# 21_Power-PMIC_RK806-1.net
KiCad netlist of a schematic drawn in Altium Designer
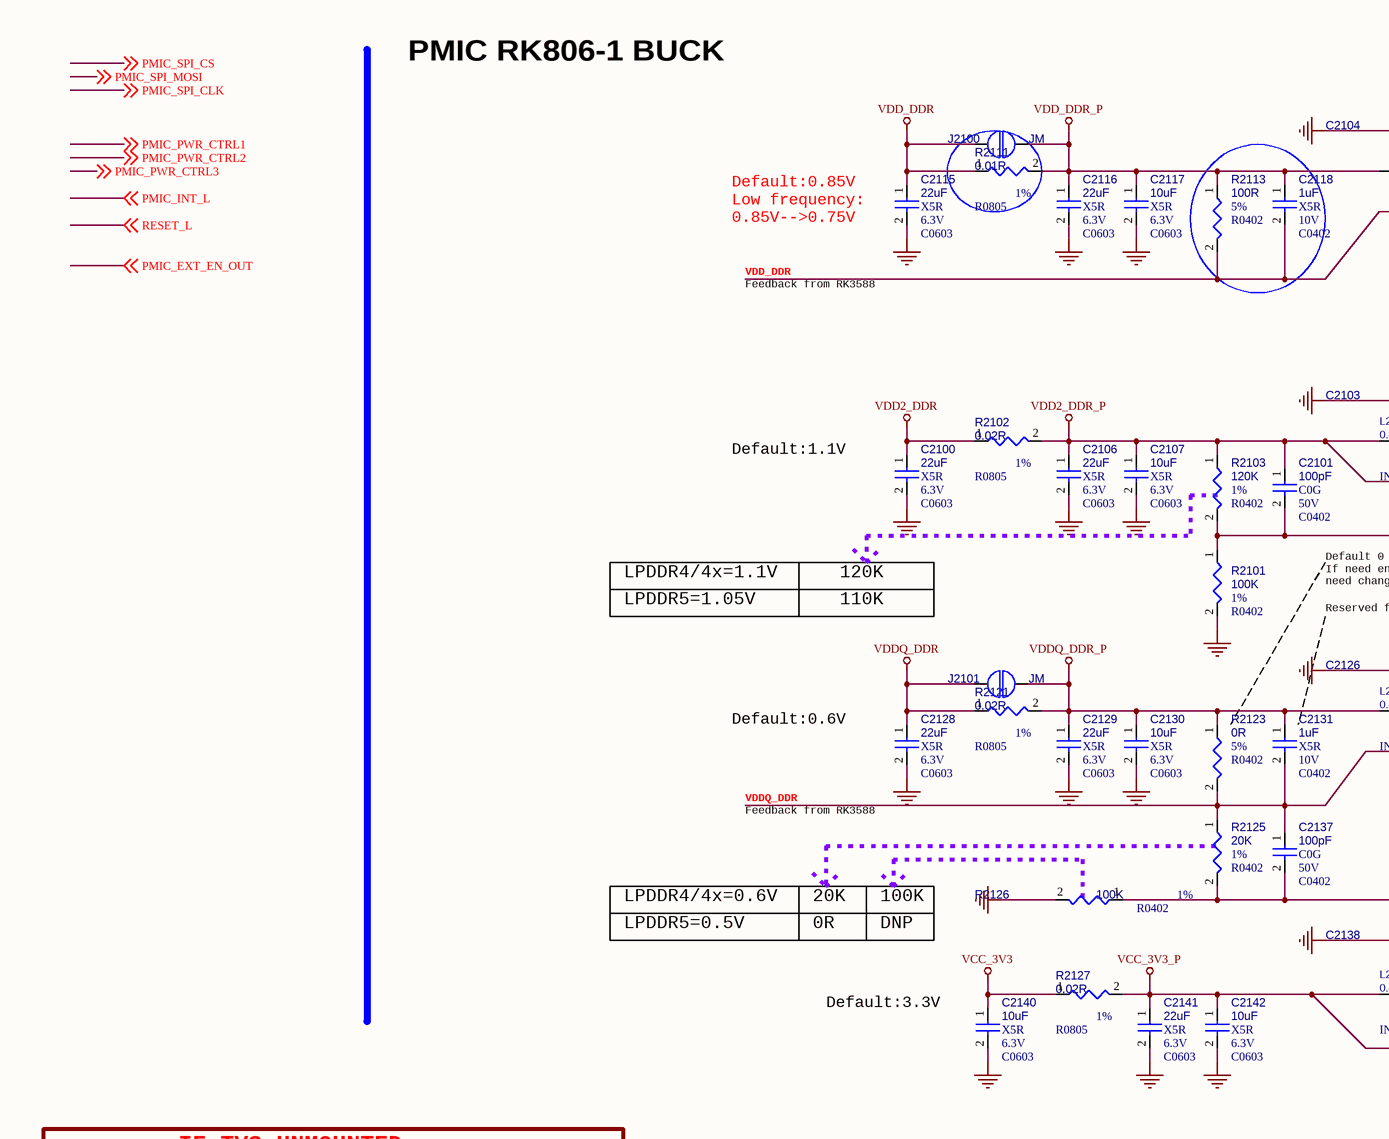
[diagram p0: 21.Power-PMIC_RK806-1.SchDoc, top left]
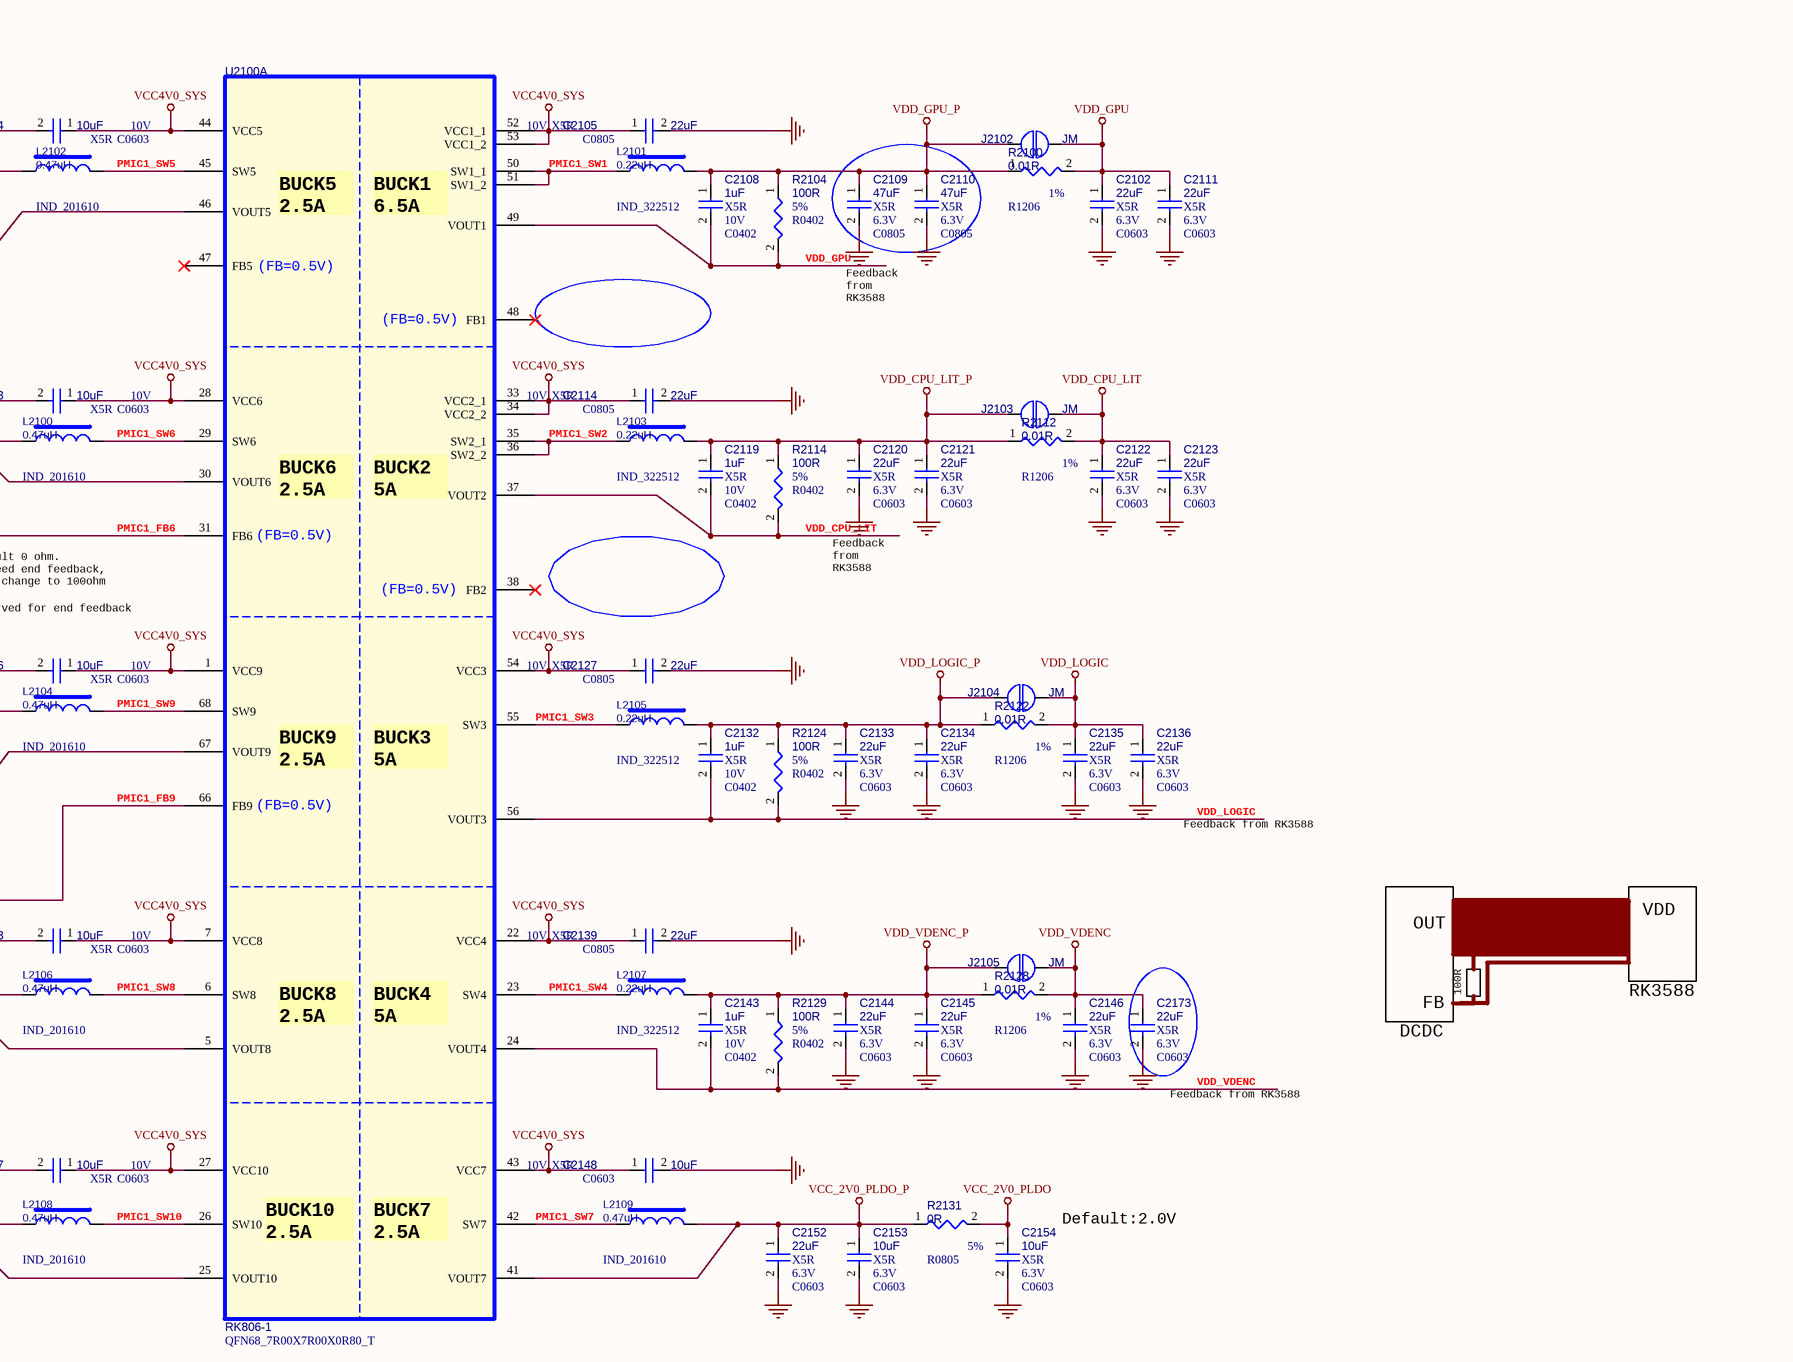
[diagram p1: 21.Power-PMIC_RK806-1.SchDoc, top right]
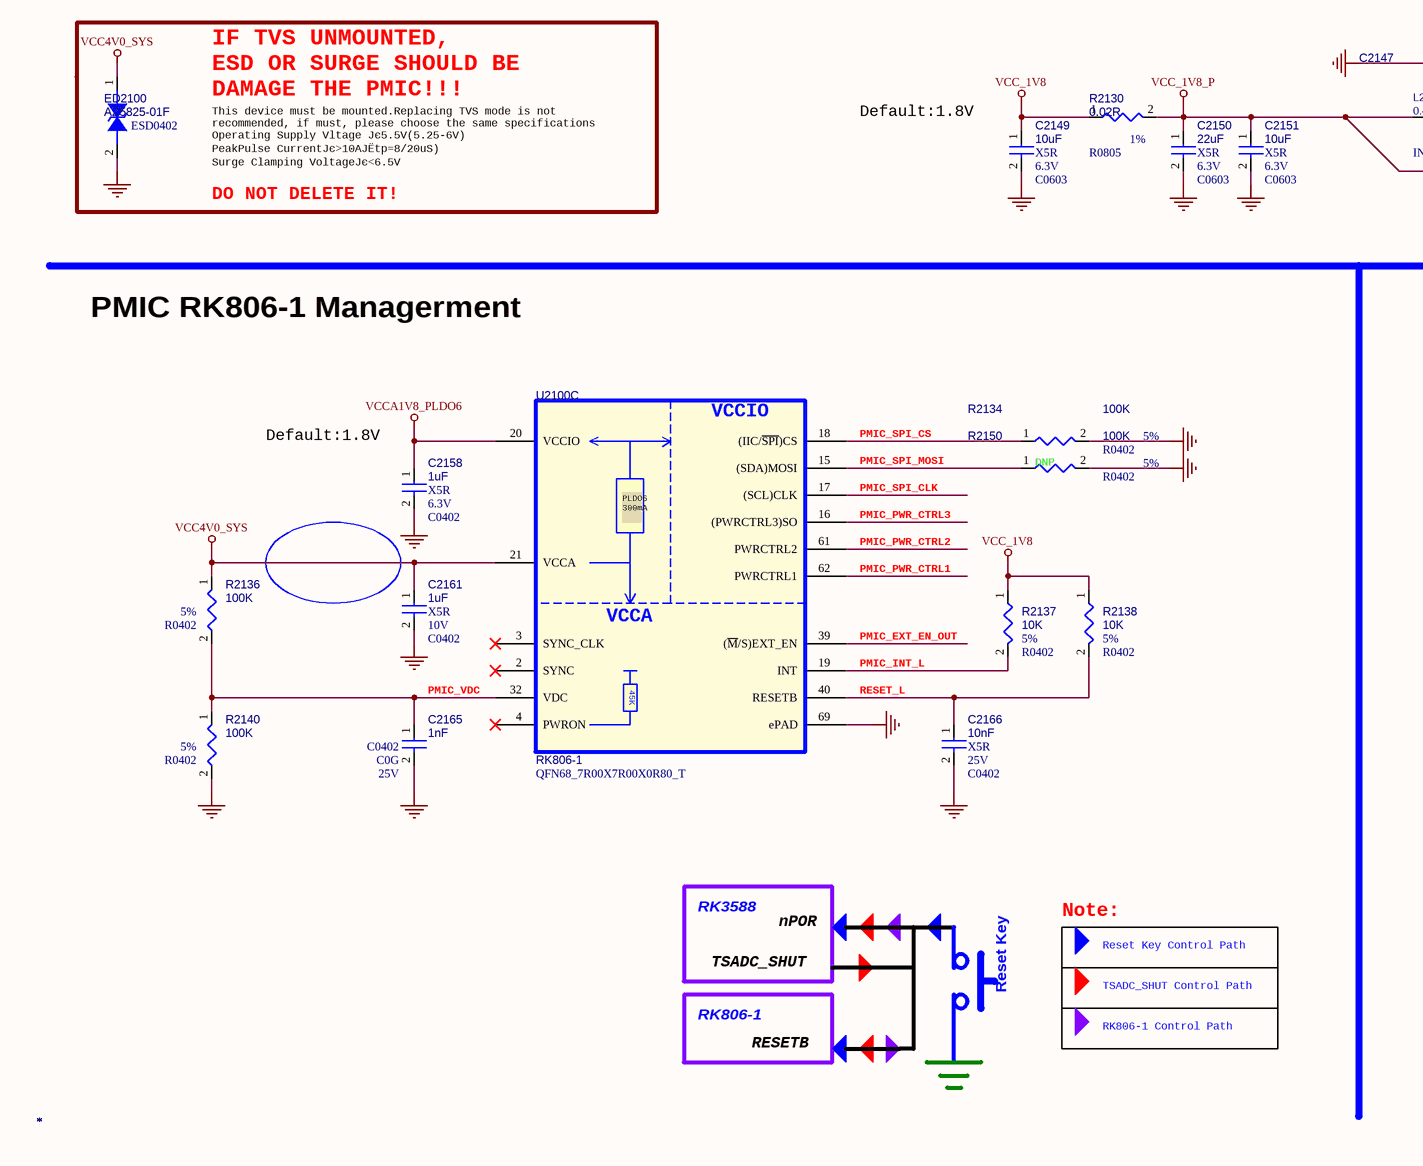
[diagram p2: 21.Power-PMIC_RK806-1.SchDoc, bottom left]
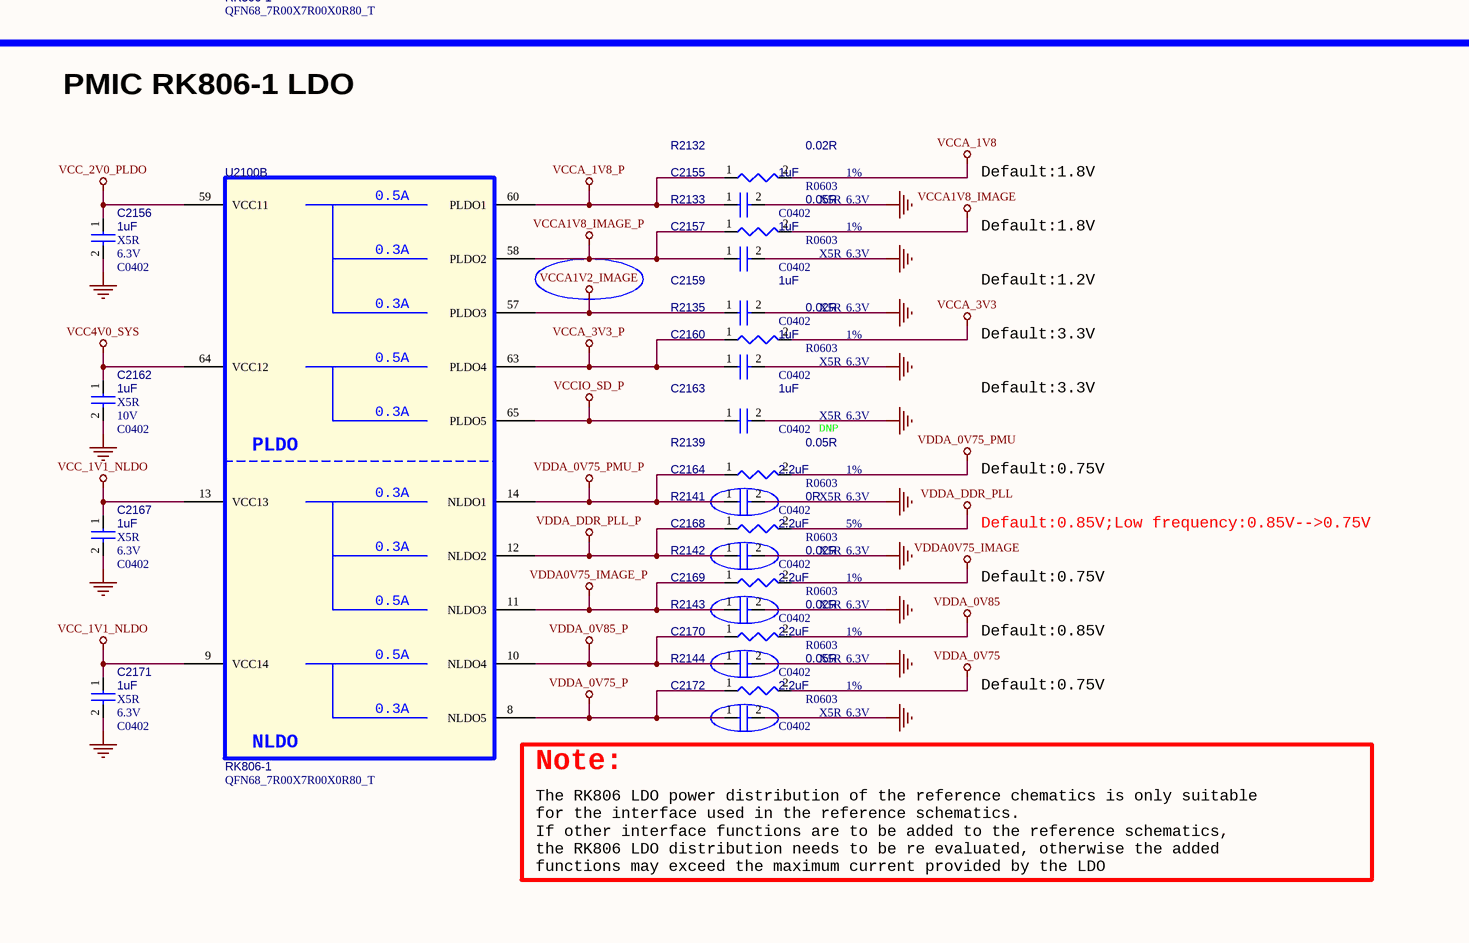
[diagram p3: 21.Power-PMIC_RK806-1.SchDoc, bottom right]

(export (version "E")
  (design (tool "Eeschema 10.0.6"))
  (components
    (comp (ref "C2100")
      (value "*")
      (footprint "C0603")
      (description "cap,22.00uF,+/-20%,6.3V,X5R,C0603")
      (fields
        (field (name "VOLTAGE") "6.3V")
        (field (name "PCB FOOTPRINT") "C0603")
        (field (name "DIELECTRIC") "X5R")
        (field (name "MANUFACTURER") "TDK")
        (field (name "TOLERANCE") "20%")
        (field (name "ALTIUM_UNNAMED_1") "22uF")
        (field (name "CREATED BY") "JJJ")
      )
      (libsource (lib "*") (part "CAP NP"))
    )
    (comp (ref "C2101")
      (value "*")
      (footprint "C0402")
      (description "cap,100.00pF,+/-10%,50V,C0G,C0402")
      (fields
        (field (name "VOLTAGE") "50V")
        (field (name "PCB FOOTPRINT") "C0402")
        (field (name "DIELECTRIC") "C0G")
        (field (name "TOLERANCE") "10%")
        (field (name "MANUFACTURER") "TDK")
        (field (name "ALTIUM_UNNAMED_1") "100pF")
        (field (name "CREATED BY") "JJJ")
      )
      (libsource (lib "*") (part "CAP NP"))
    )
    (comp (ref "C2102")
      (value "*")
      (footprint "C0603")
      (description "cap,22.00uF,+/-20%,6.3V,X5R,C0603")
      (fields
        (field (name "VOLTAGE") "6.3V")
        (field (name "PCB FOOTPRINT") "C0603")
        (field (name "DIELECTRIC") "X5R")
        (field (name "MANUFACTURER") "TDK")
        (field (name "TOLERANCE") "20%")
        (field (name "ALTIUM_UNNAMED_1") "22uF")
        (field (name "CREATED BY") "JJJ")
      )
      (libsource (lib "*") (part "CAP NP"))
    )
    (comp (ref "C2103")
      (value "*")
      (footprint "C0603")
      (description "cap,10.00uF,+/-10%,10V,X5R,C0603")
      (fields
        (field (name "VOLTAGE") "10V")
        (field (name "PCB FOOTPRINT") "C0603")
        (field (name "DIELECTRIC") "X5R")
        (field (name "MANUFACTURER") "TDK")
        (field (name "TOLERANCE") "10%")
        (field (name "ALTIUM_UNNAMED_1") "10uF")
        (field (name "CREATED BY") "JJJ")
      )
      (libsource (lib "*") (part "CAP NP"))
    )
    (comp (ref "C2104")
      (value "*")
      (footprint "C0603")
      (description "cap,10.00uF,+/-10%,10V,X5R,C0603")
      (fields
        (field (name "VOLTAGE") "10V")
        (field (name "PCB FOOTPRINT") "C0603")
        (field (name "DIELECTRIC") "X5R")
        (field (name "MANUFACTURER") "TDK")
        (field (name "TOLERANCE") "10%")
        (field (name "ALTIUM_UNNAMED_1") "10uF")
        (field (name "CREATED BY") "JJJ")
      )
      (libsource (lib "*") (part "CAP NP"))
    )
    (comp (ref "C2105")
      (value "*")
      (footprint "C0805")
      (description "cap,22.00uF,+/-10%,10V,X5R,C0805")
      (fields
        (field (name "VOLTAGE") "10V")
        (field (name "PCB FOOTPRINT") "C0805")
        (field (name "DIELECTRIC") "X5R")
        (field (name "TOLERANCE") "10%")
        (field (name "MANUFACTURER") "TDK")
        (field (name "ALTIUM_UNNAMED_1") "22uF")
        (field (name "CREATED BY") "JJJ")
      )
      (libsource (lib "*") (part "CAP NP"))
    )
    (comp (ref "C2106")
      (value "*")
      (footprint "C0603")
      (description "cap,22.00uF,+/-20%,6.3V,X5R,C0603")
      (fields
        (field (name "VOLTAGE") "6.3V")
        (field (name "PCB FOOTPRINT") "C0603")
        (field (name "DIELECTRIC") "X5R")
        (field (name "MANUFACTURER") "TDK")
        (field (name "TOLERANCE") "20%")
        (field (name "ALTIUM_UNNAMED_1") "22uF")
        (field (name "CREATED BY") "JJJ")
      )
      (libsource (lib "*") (part "CAP NP"))
    )
    (comp (ref "C2107")
      (value "*")
      (footprint "C0603")
      (description "cap,10.00uF,+/-10%,6.3V,X5R,C0603")
      (fields
        (field (name "VOLTAGE") "6.3V")
        (field (name "PCB FOOTPRINT") "C0603")
        (field (name "DIELECTRIC") "X5R")
        (field (name "MANUFACTURER") "TDK")
        (field (name "TOLERANCE") "10%")
        (field (name "ALTIUM_UNNAMED_1") "10uF")
        (field (name "CREATED BY") "JJJ")
      )
      (libsource (lib "*") (part "CAP NP"))
    )
    (comp (ref "C2108")
      (value "*")
      (footprint "C0402")
      (description "cap,1.00uF,+/-10%,10V,X5R,C0402")
      (fields
        (field (name "VOLTAGE") "10V")
        (field (name "PCB FOOTPRINT") "C0402")
        (field (name "DIELECTRIC") "X5R")
        (field (name "TOLERANCE") "10%")
        (field (name "MANUFACTURER") "TDK")
        (field (name "ALTIUM_UNNAMED_1") "1uF")
        (field (name "CREATED BY") "JJJ")
      )
      (libsource (lib "*") (part "CAP NP"))
    )
    (comp (ref "C2109")
      (value "*")
      (footprint "C0805")
      (description "cap,47.00uF,+/-20%,6.3V,X5R,C0805")
      (fields
        (field (name "VOLTAGE") "6.3V")
        (field (name "PCB FOOTPRINT") "C0805")
        (field (name "DIELECTRIC") "X5R")
        (field (name "TOLERANCE") "20%")
        (field (name "MANUFACTURER") "TDK")
        (field (name "ALTIUM_UNNAMED_1") "47uF")
        (field (name "CREATED BY") "JJJ")
      )
      (libsource (lib "*") (part "CAP NP"))
    )
    (comp (ref "C2110")
      (value "*")
      (footprint "C0805")
      (description "cap,47.00uF,+/-20%,6.3V,X5R,C0805")
      (fields
        (field (name "VOLTAGE") "6.3V")
        (field (name "PCB FOOTPRINT") "C0805")
        (field (name "DIELECTRIC") "X5R")
        (field (name "MANUFACTURER") "TDK")
        (field (name "TOLERANCE") "20%")
        (field (name "ALTIUM_UNNAMED_1") "47uF")
        (field (name "CREATED BY") "JJJ")
      )
      (libsource (lib "*") (part "CAP NP"))
    )
    (comp (ref "C2111")
      (value "*")
      (footprint "C0603")
      (description "cap,22.00uF,+/-20%,6.3V,X5R,C0603")
      (fields
        (field (name "VOLTAGE") "6.3V")
        (field (name "PCB FOOTPRINT") "C0603")
        (field (name "DIELECTRIC") "X5R")
        (field (name "MANUFACTURER") "TDK")
        (field (name "TOLERANCE") "20%")
        (field (name "ALTIUM_UNNAMED_1") "22uF")
        (field (name "CREATED BY") "JJJ")
      )
      (libsource (lib "*") (part "CAP NP"))
    )
    (comp (ref "C2114")
      (value "*")
      (footprint "C0805")
      (description "cap,22.00uF,+/-10%,10V,X5R,C0805")
      (fields
        (field (name "VOLTAGE") "10V")
        (field (name "PCB FOOTPRINT") "C0805")
        (field (name "DIELECTRIC") "X5R")
        (field (name "TOLERANCE") "10%")
        (field (name "MANUFACTURER") "TDK")
        (field (name "ALTIUM_UNNAMED_1") "22uF")
        (field (name "CREATED BY") "JJJ")
      )
      (libsource (lib "*") (part "CAP NP"))
    )
    (comp (ref "C2115")
      (value "*")
      (footprint "C0603")
      (description "cap,22.00uF,+/-20%,6.3V,X5R,C0603")
      (fields
        (field (name "VOLTAGE") "6.3V")
        (field (name "PCB FOOTPRINT") "C0603")
        (field (name "DIELECTRIC") "X5R")
        (field (name "TOLERANCE") "20%")
        (field (name "MANUFACTURER") "TDK")
        (field (name "ALTIUM_UNNAMED_1") "22uF")
        (field (name "CREATED BY") "JJJ")
      )
      (libsource (lib "*") (part "CAP NP"))
    )
    (comp (ref "C2116")
      (value "*")
      (footprint "C0603")
      (description "cap,22.00uF,+/-20%,6.3V,X5R,C0603")
      (fields
        (field (name "VOLTAGE") "6.3V")
        (field (name "PCB FOOTPRINT") "C0603")
        (field (name "DIELECTRIC") "X5R")
        (field (name "MANUFACTURER") "TDK")
        (field (name "TOLERANCE") "20%")
        (field (name "ALTIUM_UNNAMED_1") "22uF")
        (field (name "CREATED BY") "JJJ")
      )
      (libsource (lib "*") (part "CAP NP"))
    )
    (comp (ref "C2117")
      (value "*")
      (footprint "C0603")
      (description "cap,10.00uF,+/-10%,6.3V,X5R,C0603")
      (fields
        (field (name "VOLTAGE") "6.3V")
        (field (name "PCB FOOTPRINT") "C0603")
        (field (name "DIELECTRIC") "X5R")
        (field (name "MANUFACTURER") "TDK")
        (field (name "TOLERANCE") "10%")
        (field (name "ALTIUM_UNNAMED_1") "10uF")
        (field (name "CREATED BY") "JJJ")
      )
      (libsource (lib "*") (part "CAP NP"))
    )
    (comp (ref "C2118")
      (value "*")
      (footprint "C0402")
      (description "cap,1.00uF,+/-10%,10V,X5R,C0402")
      (fields
        (field (name "VOLTAGE") "10V")
        (field (name "PCB FOOTPRINT") "C0402")
        (field (name "DIELECTRIC") "X5R")
        (field (name "MANUFACTURER") "TDK")
        (field (name "TOLERANCE") "10%")
        (field (name "ALTIUM_UNNAMED_1") "1uF")
        (field (name "CREATED BY") "JJJ")
      )
      (libsource (lib "*") (part "CAP NP"))
    )
    (comp (ref "C2119")
      (value "*")
      (footprint "C0402")
      (description "cap,1.00uF,+/-10%,10V,X5R,C0402")
      (fields
        (field (name "VOLTAGE") "10V")
        (field (name "PCB FOOTPRINT") "C0402")
        (field (name "DIELECTRIC") "X5R")
        (field (name "TOLERANCE") "10%")
        (field (name "MANUFACTURER") "TDK")
        (field (name "ALTIUM_UNNAMED_1") "1uF")
        (field (name "CREATED BY") "JJJ")
      )
      (libsource (lib "*") (part "CAP NP"))
    )
    (comp (ref "C2120")
      (value "*")
      (footprint "C0603")
      (description "cap,22.00uF,+/-20%,6.3V,X5R,C0603")
      (fields
        (field (name "VOLTAGE") "6.3V")
        (field (name "PCB FOOTPRINT") "C0603")
        (field (name "DIELECTRIC") "X5R")
        (field (name "MANUFACTURER") "TDK")
        (field (name "TOLERANCE") "20%")
        (field (name "ALTIUM_UNNAMED_1") "22uF")
        (field (name "CREATED BY") "JJJ")
      )
      (libsource (lib "*") (part "CAP NP"))
    )
    (comp (ref "C2121")
      (value "*")
      (footprint "C0603")
      (description "cap,22.00uF,+/-20%,6.3V,X5R,C0603")
      (fields
        (field (name "VOLTAGE") "6.3V")
        (field (name "PCB FOOTPRINT") "C0603")
        (field (name "DIELECTRIC") "X5R")
        (field (name "MANUFACTURER") "TDK")
        (field (name "TOLERANCE") "20%")
        (field (name "ALTIUM_UNNAMED_1") "22uF")
        (field (name "CREATED BY") "JJJ")
      )
      (libsource (lib "*") (part "CAP NP"))
    )
    (comp (ref "C2122")
      (value "*")
      (footprint "C0603")
      (description "cap,22.00uF,+/-20%,6.3V,X5R,C0603")
      (fields
        (field (name "VOLTAGE") "6.3V")
        (field (name "PCB FOOTPRINT") "C0603")
        (field (name "DIELECTRIC") "X5R")
        (field (name "TOLERANCE") "20%")
        (field (name "MANUFACTURER") "TDK")
        (field (name "ALTIUM_UNNAMED_1") "22uF")
        (field (name "CREATED BY") "JJJ")
      )
      (libsource (lib "*") (part "CAP NP"))
    )
    (comp (ref "C2123")
      (value "*")
      (footprint "C0603")
      (description "cap,22.00uF,+/-20%,6.3V,X5R,C0603")
      (fields
        (field (name "VOLTAGE") "6.3V")
        (field (name "PCB FOOTPRINT") "C0603")
        (field (name "DIELECTRIC") "X5R")
        (field (name "TOLERANCE") "20%")
        (field (name "MANUFACTURER") "TDK")
        (field (name "ALTIUM_UNNAMED_1") "22uF")
        (field (name "CREATED BY") "JJJ")
      )
      (libsource (lib "*") (part "CAP NP"))
    )
    (comp (ref "C2126")
      (value "*")
      (footprint "C0603")
      (description "cap,10.00uF,+/-10%,10V,X5R,C0603")
      (fields
        (field (name "VOLTAGE") "10V")
        (field (name "PCB FOOTPRINT") "C0603")
        (field (name "DIELECTRIC") "X5R")
        (field (name "MANUFACTURER") "TDK")
        (field (name "TOLERANCE") "10%")
        (field (name "ALTIUM_UNNAMED_1") "10uF")
        (field (name "CREATED BY") "JJJ")
      )
      (libsource (lib "*") (part "CAP NP"))
    )
    (comp (ref "C2127")
      (value "*")
      (footprint "C0805")
      (description "cap,22.00uF,+/-10%,10V,X5R,C0805")
      (fields
        (field (name "VOLTAGE") "10V")
        (field (name "PCB FOOTPRINT") "C0805")
        (field (name "DIELECTRIC") "X5R")
        (field (name "TOLERANCE") "10%")
        (field (name "MANUFACTURER") "TDK")
        (field (name "ALTIUM_UNNAMED_1") "22uF")
        (field (name "CREATED BY") "JJJ")
      )
      (libsource (lib "*") (part "CAP NP"))
    )
    (comp (ref "C2128")
      (value "*")
      (footprint "C0603")
      (description "cap,22.00uF,+/-20%,6.3V,X5R,C0603")
      (fields
        (field (name "VOLTAGE") "6.3V")
        (field (name "PCB FOOTPRINT") "C0603")
        (field (name "DIELECTRIC") "X5R")
        (field (name "MANUFACTURER") "TDK")
        (field (name "TOLERANCE") "20%")
        (field (name "ALTIUM_UNNAMED_1") "22uF")
        (field (name "CREATED BY") "JJJ")
      )
      (libsource (lib "*") (part "CAP NP"))
    )
    (comp (ref "C2129")
      (value "*")
      (footprint "C0603")
      (description "cap,22.00uF,+/-20%,6.3V,X5R,C0603")
      (fields
        (field (name "VOLTAGE") "6.3V")
        (field (name "PCB FOOTPRINT") "C0603")
        (field (name "DIELECTRIC") "X5R")
        (field (name "MANUFACTURER") "TDK")
        (field (name "TOLERANCE") "20%")
        (field (name "ALTIUM_UNNAMED_1") "22uF")
        (field (name "CREATED BY") "JJJ")
      )
      (libsource (lib "*") (part "CAP NP"))
    )
    (comp (ref "C2130")
      (value "*")
      (footprint "C0603")
      (description "cap,10.00uF,+/-10%,6.3V,X5R,C0603")
      (fields
        (field (name "VOLTAGE") "6.3V")
        (field (name "PCB FOOTPRINT") "C0603")
        (field (name "DIELECTRIC") "X5R")
        (field (name "MANUFACTURER") "TDK")
        (field (name "TOLERANCE") "10%")
        (field (name "ALTIUM_UNNAMED_1") "10uF")
        (field (name "CREATED BY") "JJJ")
      )
      (libsource (lib "*") (part "CAP NP"))
    )
    (comp (ref "C2131")
      (value "*")
      (footprint "C0402")
      (description "cap,1.00uF,+/-10%,10V,X5R,C0402")
      (fields
        (field (name "VOLTAGE") "10V")
        (field (name "PCB FOOTPRINT") "C0402")
        (field (name "DIELECTRIC") "X5R")
        (field (name "MANUFACTURER") "TDK")
        (field (name "TOLERANCE") "10%")
        (field (name "ALTIUM_UNNAMED_1") "1uF")
        (field (name "CREATED BY") "JJJ")
      )
      (libsource (lib "*") (part "CAP NP"))
    )
    (comp (ref "C2132")
      (value "*")
      (footprint "C0402")
      (description "cap,1.00uF,+/-10%,10V,X5R,C0402")
      (fields
        (field (name "VOLTAGE") "10V")
        (field (name "PCB FOOTPRINT") "C0402")
        (field (name "DIELECTRIC") "X5R")
        (field (name "TOLERANCE") "10%")
        (field (name "MANUFACTURER") "TDK")
        (field (name "ALTIUM_UNNAMED_1") "1uF")
        (field (name "CREATED BY") "JJJ")
      )
      (libsource (lib "*") (part "CAP NP"))
    )
    (comp (ref "C2133")
      (value "*")
      (footprint "C0603")
      (description "cap,22.00uF,+/-20%,6.3V,X5R,C0603")
      (fields
        (field (name "VOLTAGE") "6.3V")
        (field (name "PCB FOOTPRINT") "C0603")
        (field (name "DIELECTRIC") "X5R")
        (field (name "MANUFACTURER") "TDK")
        (field (name "TOLERANCE") "20%")
        (field (name "ALTIUM_UNNAMED_1") "22uF")
        (field (name "CREATED BY") "JJJ")
      )
      (libsource (lib "*") (part "CAP NP"))
    )
    (comp (ref "C2134")
      (value "*")
      (footprint "C0603")
      (description "cap,22.00uF,+/-20%,6.3V,X5R,C0603")
      (fields
        (field (name "VOLTAGE") "6.3V")
        (field (name "PCB FOOTPRINT") "C0603")
        (field (name "DIELECTRIC") "X5R")
        (field (name "MANUFACTURER") "TDK")
        (field (name "TOLERANCE") "20%")
        (field (name "ALTIUM_UNNAMED_1") "22uF")
        (field (name "CREATED BY") "JJJ")
      )
      (libsource (lib "*") (part "CAP NP"))
    )
    (comp (ref "C2135")
      (value "*")
      (footprint "C0603")
      (description "cap,22.00uF,+/-20%,6.3V,X5R,C0603")
      (fields
        (field (name "VOLTAGE") "6.3V")
        (field (name "PCB FOOTPRINT") "C0603")
        (field (name "DIELECTRIC") "X5R")
        (field (name "MANUFACTURER") "TDK")
        (field (name "TOLERANCE") "20%")
        (field (name "ALTIUM_UNNAMED_1") "22uF")
        (field (name "CREATED BY") "JJJ")
      )
      (libsource (lib "*") (part "CAP NP"))
    )
    (comp (ref "C2136")
      (value "*")
      (footprint "C0603")
      (description "cap,22.00uF,+/-20%,6.3V,X5R,C0603")
      (fields
        (field (name "VOLTAGE") "6.3V")
        (field (name "PCB FOOTPRINT") "C0603")
        (field (name "DIELECTRIC") "X5R")
        (field (name "MANUFACTURER") "TDK")
        (field (name "TOLERANCE") "20%")
        (field (name "ALTIUM_UNNAMED_1") "22uF")
        (field (name "CREATED BY") "JJJ")
      )
      (libsource (lib "*") (part "CAP NP"))
    )
    (comp (ref "C2137")
      (value "*")
      (footprint "C0402")
      (description "cap,100.00pF,+/-10%,50V,C0G,C0402")
      (fields
        (field (name "VOLTAGE") "50V")
        (field (name "PCB FOOTPRINT") "C0402")
        (field (name "DIELECTRIC") "C0G")
        (field (name "TOLERANCE") "10%")
        (field (name "MANUFACTURER") "TDK")
        (field (name "ALTIUM_UNNAMED_1") "100pF")
        (field (name "CREATED BY") "JJJ")
      )
      (libsource (lib "*") (part "CAP NP"))
    )
    (comp (ref "C2138")
      (value "*")
      (footprint "C0603")
      (description "cap,10.00uF,+/-10%,10V,X5R,C0603")
      (fields
        (field (name "VOLTAGE") "10V")
        (field (name "PCB FOOTPRINT") "C0603")
        (field (name "DIELECTRIC") "X5R")
        (field (name "MANUFACTURER") "TDK")
        (field (name "TOLERANCE") "10%")
        (field (name "ALTIUM_UNNAMED_1") "10uF")
        (field (name "CREATED BY") "JJJ")
      )
      (libsource (lib "*") (part "CAP NP"))
    )
    (comp (ref "C2139")
      (value "*")
      (footprint "C0805")
      (description "cap,22.00uF,+/-10%,10V,X5R,C0805")
      (fields
        (field (name "VOLTAGE") "10V")
        (field (name "PCB FOOTPRINT") "C0805")
        (field (name "DIELECTRIC") "X5R")
        (field (name "TOLERANCE") "10%")
        (field (name "MANUFACTURER") "TDK")
        (field (name "ALTIUM_UNNAMED_1") "22uF")
        (field (name "CREATED BY") "JJJ")
      )
      (libsource (lib "*") (part "CAP NP"))
    )
    (comp (ref "C2140")
      (value "*")
      (footprint "C0603")
      (description "cap,10.00uF,+/-10%,6.3V,X5R,C0603")
      (fields
        (field (name "VOLTAGE") "6.3V")
        (field (name "PCB FOOTPRINT") "C0603")
        (field (name "DIELECTRIC") "X5R")
        (field (name "TOLERANCE") "10%")
        (field (name "MANUFACTURER") "TDK")
        (field (name "ALTIUM_UNNAMED_1") "10uF")
        (field (name "CREATED BY") "JJJ")
      )
      (libsource (lib "*") (part "CAP NP"))
    )
    (comp (ref "C2141")
      (value "*")
      (footprint "C0603")
      (description "cap,22.00uF,+/-20%,6.3V,X5R,C0603")
      (fields
        (field (name "VOLTAGE") "6.3V")
        (field (name "PCB FOOTPRINT") "C0603")
        (field (name "DIELECTRIC") "X5R")
        (field (name "MANUFACTURER") "TDK")
        (field (name "TOLERANCE") "20%")
        (field (name "ALTIUM_UNNAMED_1") "22uF")
        (field (name "CREATED BY") "JJJ")
      )
      (libsource (lib "*") (part "CAP NP"))
    )
    (comp (ref "C2142")
      (value "*")
      (footprint "C0603")
      (description "cap,10.00uF,+/-10%,6.3V,X5R,C0603")
      (fields
        (field (name "VOLTAGE") "6.3V")
        (field (name "PCB FOOTPRINT") "C0603")
        (field (name "DIELECTRIC") "X5R")
        (field (name "MANUFACTURER") "TDK")
        (field (name "TOLERANCE") "10%")
        (field (name "ALTIUM_UNNAMED_1") "10uF")
        (field (name "CREATED BY") "JJJ")
      )
      (libsource (lib "*") (part "CAP NP"))
    )
    (comp (ref "C2143")
      (value "*")
      (footprint "C0402")
      (description "cap,1.00uF,+/-10%,10V,X5R,C0402")
      (fields
        (field (name "VOLTAGE") "10V")
        (field (name "PCB FOOTPRINT") "C0402")
        (field (name "DIELECTRIC") "X5R")
        (field (name "TOLERANCE") "10%")
        (field (name "MANUFACTURER") "TDK")
        (field (name "ALTIUM_UNNAMED_1") "1uF")
        (field (name "CREATED BY") "JJJ")
      )
      (libsource (lib "*") (part "CAP NP"))
    )
    (comp (ref "C2144")
      (value "*")
      (footprint "C0603")
      (description "cap,22.00uF,+/-20%,6.3V,X5R,C0603")
      (fields
        (field (name "VOLTAGE") "6.3V")
        (field (name "PCB FOOTPRINT") "C0603")
        (field (name "DIELECTRIC") "X5R")
        (field (name "TOLERANCE") "20%")
        (field (name "MANUFACTURER") "TDK")
        (field (name "ALTIUM_UNNAMED_1") "22uF")
        (field (name "CREATED BY") "JJJ")
      )
      (libsource (lib "*") (part "CAP NP"))
    )
    (comp (ref "C2145")
      (value "*")
      (footprint "C0603")
      (description "cap,22.00uF,+/-20%,6.3V,X5R,C0603")
      (fields
        (field (name "VOLTAGE") "6.3V")
        (field (name "PCB FOOTPRINT") "C0603")
        (field (name "DIELECTRIC") "X5R")
        (field (name "TOLERANCE") "20%")
        (field (name "MANUFACTURER") "TDK")
        (field (name "ALTIUM_UNNAMED_1") "22uF")
        (field (name "CREATED BY") "JJJ")
      )
      (libsource (lib "*") (part "CAP NP"))
    )
    (comp (ref "C2146")
      (value "*")
      (footprint "C0603")
      (description "cap,22.00uF,+/-20%,6.3V,X5R,C0603")
      (fields
        (field (name "VOLTAGE") "6.3V")
        (field (name "PCB FOOTPRINT") "C0603")
        (field (name "DIELECTRIC") "X5R")
        (field (name "TOLERANCE") "20%")
        (field (name "MANUFACTURER") "TDK")
        (field (name "ALTIUM_UNNAMED_1") "22uF")
        (field (name "CREATED BY") "JJJ")
      )
      (libsource (lib "*") (part "CAP NP"))
    )
    (comp (ref "C2147")
      (value "*")
      (footprint "C0603")
      (description "cap,10.00uF,+/-10%,10V,X5R,C0603")
      (fields
        (field (name "VOLTAGE") "10V")
        (field (name "PCB FOOTPRINT") "C0603")
        (field (name "DIELECTRIC") "X5R")
        (field (name "TOLERANCE") "10%")
        (field (name "MANUFACTURER") "TDK")
        (field (name "ALTIUM_UNNAMED_1") "10uF")
        (field (name "CREATED BY") "JJJ")
      )
      (libsource (lib "*") (part "CAP NP"))
    )
    (comp (ref "C2148")
      (value "*")
      (footprint "C0603")
      (description "cap,10.00uF,+/-10%,10V,X5R,C0603")
      (fields
        (field (name "VOLTAGE") "10V")
        (field (name "PCB FOOTPRINT") "C0603")
        (field (name "DIELECTRIC") "X5R")
        (field (name "TOLERANCE") "10%")
        (field (name "MANUFACTURER") "TDK")
        (field (name "ALTIUM_UNNAMED_1") "10uF")
        (field (name "CREATED BY") "JJJ")
      )
      (libsource (lib "*") (part "CAP NP"))
    )
    (comp (ref "C2149")
      (value "*")
      (footprint "C0603")
      (description "cap,10.00uF,+/-10%,6.3V,X5R,C0603")
      (fields
        (field (name "VOLTAGE") "6.3V")
        (field (name "PCB FOOTPRINT") "C0603")
        (field (name "DIELECTRIC") "X5R")
        (field (name "TOLERANCE") "10%")
        (field (name "MANUFACTURER") "TDK")
        (field (name "ALTIUM_UNNAMED_1") "10uF")
        (field (name "CREATED BY") "JJJ")
      )
      (libsource (lib "*") (part "CAP NP"))
    )
    (comp (ref "C2150")
      (value "*")
      (footprint "C0603")
      (description "cap,22.00uF,+/-20%,6.3V,X5R,C0603")
      (fields
        (field (name "VOLTAGE") "6.3V")
        (field (name "PCB FOOTPRINT") "C0603")
        (field (name "DIELECTRIC") "X5R")
        (field (name "MANUFACTURER") "TDK")
        (field (name "TOLERANCE") "20%")
        (field (name "ALTIUM_UNNAMED_1") "22uF")
        (field (name "CREATED BY") "JJJ")
      )
      (libsource (lib "*") (part "CAP NP"))
    )
    (comp (ref "C2151")
      (value "*")
      (footprint "C0603")
      (description "cap,10.00uF,+/-10%,6.3V,X5R,C0603")
      (fields
        (field (name "VOLTAGE") "6.3V")
        (field (name "PCB FOOTPRINT") "C0603")
        (field (name "DIELECTRIC") "X5R")
        (field (name "MANUFACTURER") "TDK")
        (field (name "TOLERANCE") "10%")
        (field (name "ALTIUM_UNNAMED_1") "10uF")
        (field (name "CREATED BY") "JJJ")
      )
      (libsource (lib "*") (part "CAP NP"))
    )
    (comp (ref "C2152")
      (value "*")
      (footprint "C0603")
      (description "cap,22.00uF,+/-20%,6.3V,X5R,C0603")
      (fields
        (field (name "VOLTAGE") "6.3V")
        (field (name "PCB FOOTPRINT") "C0603")
        (field (name "DIELECTRIC") "X5R")
        (field (name "MANUFACTURER") "TDK")
        (field (name "TOLERANCE") "20%")
        (field (name "ALTIUM_UNNAMED_1") "22uF")
        (field (name "CREATED BY") "JJJ")
      )
      (libsource (lib "*") (part "CAP NP"))
    )
    (comp (ref "C2153")
      (value "*")
      (footprint "C0603")
      (description "cap,10.00uF,+/-10%,6.3V,X5R,C0603")
      (fields
        (field (name "VOLTAGE") "6.3V")
        (field (name "PCB FOOTPRINT") "C0603")
        (field (name "DIELECTRIC") "X5R")
        (field (name "MANUFACTURER") "TDK")
        (field (name "TOLERANCE") "10%")
        (field (name "ALTIUM_UNNAMED_1") "10uF")
        (field (name "CREATED BY") "JJJ")
      )
      (libsource (lib "*") (part "CAP NP"))
    )
    (comp (ref "C2154")
      (value "*")
      (footprint "C0603")
      (description "cap,10.00uF,+/-10%,6.3V,X5R,C0603")
      (fields
        (field (name "VOLTAGE") "6.3V")
        (field (name "PCB FOOTPRINT") "C0603")
        (field (name "DIELECTRIC") "X5R")
        (field (name "MANUFACTURER") "TDK")
        (field (name "TOLERANCE") "10%")
        (field (name "ALTIUM_UNNAMED_1") "10uF")
        (field (name "CREATED BY") "JJJ")
      )
      (libsource (lib "*") (part "CAP NP"))
    )
    (comp (ref "C2155")
      (value "*")
      (footprint "C0402")
      (description "cap,1.00uF,+/-10%,6.3V,X5R,C0402")
      (fields
        (field (name "VOLTAGE") "6.3V")
        (field (name "PCB FOOTPRINT") "C0402")
        (field (name "DIELECTRIC") "X5R")
        (field (name "MANUFACTURER") "TDK")
        (field (name "TOLERANCE") "10%")
        (field (name "ALTIUM_UNNAMED_1") "1uF")
        (field (name "CREATED BY") "JJJ")
      )
      (libsource (lib "*") (part "CAP NP"))
    )
    (comp (ref "C2156")
      (value "*")
      (footprint "C0402")
      (description "cap,1.00uF,+/-10%,6.3V,X5R,C0402")
      (fields
        (field (name "VOLTAGE") "6.3V")
        (field (name "PCB FOOTPRINT") "C0402")
        (field (name "DIELECTRIC") "X5R")
        (field (name "TOLERANCE") "10%")
        (field (name "MANUFACTURER") "TDK")
        (field (name "ALTIUM_UNNAMED_1") "1uF")
        (field (name "CREATED BY") "JJJ")
      )
      (libsource (lib "*") (part "CAP NP"))
    )
    (comp (ref "C2157")
      (value "*")
      (footprint "C0402")
      (description "cap,1.00uF,+/-10%,6.3V,X5R,C0402")
      (fields
        (field (name "VOLTAGE") "6.3V")
        (field (name "PCB FOOTPRINT") "C0402")
        (field (name "DIELECTRIC") "X5R")
        (field (name "TOLERANCE") "10%")
        (field (name "MANUFACTURER") "TDK")
        (field (name "ALTIUM_UNNAMED_1") "1uF")
        (field (name "CREATED BY") "JJJ")
      )
      (libsource (lib "*") (part "CAP NP"))
    )
    (comp (ref "C2158")
      (value "*")
      (footprint "C0402")
      (description "cap,1.00uF,+/-10%,6.3V,X5R,C0402")
      (fields
        (field (name "VOLTAGE") "6.3V")
        (field (name "PCB FOOTPRINT") "C0402")
        (field (name "DIELECTRIC") "X5R")
        (field (name "TOLERANCE") "10%")
        (field (name "MANUFACTURER") "TDK")
        (field (name "ALTIUM_UNNAMED_1") "1uF")
        (field (name "CREATED BY") "JJJ")
      )
      (libsource (lib "*") (part "CAP NP"))
    )
    (comp (ref "C2159")
      (value "*")
      (footprint "C0402")
      (description "cap,1.00uF,+/-10%,6.3V,X5R,C0402")
      (fields
        (field (name "VOLTAGE") "6.3V")
        (field (name "PCB FOOTPRINT") "C0402")
        (field (name "DIELECTRIC") "X5R")
        (field (name "MANUFACTURER") "TDK")
        (field (name "TOLERANCE") "10%")
        (field (name "ALTIUM_UNNAMED_1") "1uF")
        (field (name "CREATED BY") "JJJ")
      )
      (libsource (lib "*") (part "CAP NP"))
    )
    (comp (ref "C2160")
      (value "*")
      (footprint "C0402")
      (description "cap,1.00uF,+/-10%,6.3V,X5R,C0402")
      (fields
        (field (name "VOLTAGE") "6.3V")
        (field (name "PCB FOOTPRINT") "C0402")
        (field (name "DIELECTRIC") "X5R")
        (field (name "TOLERANCE") "10%")
        (field (name "MANUFACTURER") "TDK")
        (field (name "ALTIUM_UNNAMED_1") "1uF")
        (field (name "CREATED BY") "JJJ")
      )
      (libsource (lib "*") (part "CAP NP"))
    )
    (comp (ref "C2161")
      (value "*")
      (footprint "C0402")
      (description "cap,1.00uF,+/-10%,10V,X5R,C0402")
      (fields
        (field (name "VOLTAGE") "10V")
        (field (name "PCB FOOTPRINT") "C0402")
        (field (name "DIELECTRIC") "X5R")
        (field (name "TOLERANCE") "10%")
        (field (name "MANUFACTURER") "TDK")
        (field (name "ALTIUM_UNNAMED_1") "1uF")
        (field (name "CREATED BY") "JJJ")
      )
      (libsource (lib "*") (part "CAP NP"))
    )
    (comp (ref "C2162")
      (value "*")
      (footprint "C0402")
      (description "cap,1.00uF,+/-10%,10V,X5R,C0402")
      (fields
        (field (name "VOLTAGE") "10V")
        (field (name "PCB FOOTPRINT") "C0402")
        (field (name "DIELECTRIC") "X5R")
        (field (name "TOLERANCE") "10%")
        (field (name "MANUFACTURER") "TDK")
        (field (name "ALTIUM_UNNAMED_1") "1uF")
        (field (name "CREATED BY") "JJJ")
      )
      (libsource (lib "*") (part "CAP NP"))
    )
    (comp (ref "C2163")
      (value "*")
      (footprint "C0402")
      (description "cap,1.00uF,+/-10%,6.3V,X5R,C0402")
      (fields
        (field (name "VOLTAGE") "6.3V")
        (field (name "PCB FOOTPRINT") "C0402")
        (field (name "DIELECTRIC") "X5R")
        (field (name "MANUFACTURER") "TDK")
        (field (name "TOLERANCE") "10%")
        (field (name "OPTION") "DNP")
        (field (name "ALTIUM_UNNAMED_1") "1uF")
        (field (name "CREATED BY") "JJJ")
      )
      (libsource (lib "*") (part "CAP NP"))
    )
    (comp (ref "C2164")
      (value "*")
      (footprint "C0402")
      (description "cap,2.20uF,+/-10%,6.3V,X5R,C0402")
      (fields
        (field (name "VOLTAGE") "6.3V")
        (field (name "PCB FOOTPRINT") "C0402")
        (field (name "DIELECTRIC") "X5R")
        (field (name "TOLERANCE") "10%")
        (field (name "MANUFACTURER") "TDK")
        (field (name "ALTIUM_UNNAMED_1") "2.2uF")
        (field (name "CREATED BY") "JJJ")
      )
      (libsource (lib "*") (part "CAP NP"))
    )
    (comp (ref "C2165")
      (value "*")
      (footprint "C0402")
      (description "cap,1.00nF,+/-5%,25V,C0G,C0402")
      (fields
        (field (name "VOLTAGE") "25V")
        (field (name "PCB FOOTPRINT") "C0402")
        (field (name "DIELECTRIC") "C0G")
        (field (name "TOLERANCE") "5%")
        (field (name "MANUFACTURER") "TDK")
        (field (name "ALTIUM_UNNAMED_1") "1nF")
        (field (name "CREATED BY") "JJJ")
      )
      (libsource (lib "*") (part "CAP NP"))
    )
    (comp (ref "C2166")
      (value "*")
      (footprint "C0402")
      (description "cap,10.00nF,+/-10%,25V,X5R,C0402")
      (fields
        (field (name "VOLTAGE") "25V")
        (field (name "PCB FOOTPRINT") "C0402")
        (field (name "DIELECTRIC") "X5R")
        (field (name "TOLERANCE") "10%")
        (field (name "MANUFACTURER") "TDK")
        (field (name "ALTIUM_UNNAMED_1") "10nF")
        (field (name "CREATED BY") "JJJ")
      )
      (libsource (lib "*") (part "CAP NP"))
    )
    (comp (ref "C2167")
      (value "*")
      (footprint "C0402")
      (description "cap,1.00uF,+/-10%,6.3V,X5R,C0402")
      (fields
        (field (name "VOLTAGE") "6.3V")
        (field (name "PCB FOOTPRINT") "C0402")
        (field (name "DIELECTRIC") "X5R")
        (field (name "TOLERANCE") "10%")
        (field (name "MANUFACTURER") "TDK")
        (field (name "ALTIUM_UNNAMED_1") "1uF")
        (field (name "CREATED BY") "JJJ")
      )
      (libsource (lib "*") (part "CAP NP"))
    )
    (comp (ref "C2168")
      (value "*")
      (footprint "C0402")
      (description "cap,2.20uF,+/-10%,6.3V,X5R,C0402")
      (fields
        (field (name "VOLTAGE") "6.3V")
        (field (name "PCB FOOTPRINT") "C0402")
        (field (name "DIELECTRIC") "X5R")
        (field (name "TOLERANCE") "10%")
        (field (name "MANUFACTURER") "TDK")
        (field (name "ALTIUM_UNNAMED_1") "2.2uF")
        (field (name "CREATED BY") "JJJ")
      )
      (libsource (lib "*") (part "CAP NP"))
    )
    (comp (ref "C2169")
      (value "*")
      (footprint "C0402")
      (description "cap,2.20uF,+/-10%,6.3V,X5R,C0402")
      (fields
        (field (name "VOLTAGE") "6.3V")
        (field (name "PCB FOOTPRINT") "C0402")
        (field (name "DIELECTRIC") "X5R")
        (field (name "TOLERANCE") "10%")
        (field (name "MANUFACTURER") "TDK")
        (field (name "ALTIUM_UNNAMED_1") "2.2uF")
        (field (name "CREATED BY") "JJJ")
      )
      (libsource (lib "*") (part "CAP NP"))
    )
    (comp (ref "C2170")
      (value "*")
      (footprint "C0402")
      (description "cap,2.20uF,+/-10%,6.3V,X5R,C0402")
      (fields
        (field (name "VOLTAGE") "6.3V")
        (field (name "PCB FOOTPRINT") "C0402")
        (field (name "DIELECTRIC") "X5R")
        (field (name "TOLERANCE") "10%")
        (field (name "MANUFACTURER") "TDK")
        (field (name "ALTIUM_UNNAMED_1") "2.2uF")
        (field (name "CREATED BY") "JJJ")
      )
      (libsource (lib "*") (part "CAP NP"))
    )
    (comp (ref "C2171")
      (value "*")
      (footprint "C0402")
      (description "cap,1.00uF,+/-10%,6.3V,X5R,C0402")
      (fields
        (field (name "VOLTAGE") "6.3V")
        (field (name "PCB FOOTPRINT") "C0402")
        (field (name "DIELECTRIC") "X5R")
        (field (name "TOLERANCE") "10%")
        (field (name "MANUFACTURER") "TDK")
        (field (name "ALTIUM_UNNAMED_1") "1uF")
        (field (name "CREATED BY") "JJJ")
      )
      (libsource (lib "*") (part "CAP NP"))
    )
    (comp (ref "C2172")
      (value "*")
      (footprint "C0402")
      (description "cap,2.20uF,+/-10%,6.3V,X5R,C0402")
      (fields
        (field (name "VOLTAGE") "6.3V")
        (field (name "PCB FOOTPRINT") "C0402")
        (field (name "DIELECTRIC") "X5R")
        (field (name "TOLERANCE") "10%")
        (field (name "MANUFACTURER") "TDK")
        (field (name "ALTIUM_UNNAMED_1") "2.2uF")
        (field (name "CREATED BY") "JJJ")
      )
      (libsource (lib "*") (part "CAP NP"))
    )
    (comp (ref "C2173")
      (value "*")
      (footprint "C0603")
      (description "cap,22.00uF,+/-20%,6.3V,X5R,C0603")
      (fields
        (field (name "VOLTAGE") "6.3V")
        (field (name "PCB FOOTPRINT") "C0603")
        (field (name "DIELECTRIC") "X5R")
        (field (name "MANUFACTURER") "TDK")
        (field (name "TOLERANCE") "20%")
        (field (name "ALTIUM_UNNAMED_1") "22uF")
        (field (name "CREATED BY") "JJJ")
      )
      (libsource (lib "*") (part "CAP NP"))
    )
    (comp (ref "ED2100")
      (value "*")
      (footprint "ESD0402")
      (description "Transient Voltage Suppressing Device.Tiny Packge for ESD/Transient Protection")
      (fields
        (field (name "PCB FOOTPRINT") "ESD0402")
        (field (name "MANUFACTURER") "AmazingЈЁѕ§мНїЖјјЈ©")
        (field (name "ALTIUM_UNNAMED_1") "AZ5825-01F")
        (field (name "CREATED BY") "JJJ")
      )
      (libsource (lib "*") (part "DIODE BI_DIR TRIG"))
    )
    (comp (ref "J2100")
      (value "*")
      (footprint "OPEN")
      (fields (field (name "ALTIUM_UNNAMED_1") "JM"))
      (libsource (lib "*") (part "JM_0"))
    )
    (comp (ref "J2101")
      (value "*")
      (footprint "OPEN")
      (fields (field (name "ALTIUM_UNNAMED_1") "JM"))
      (libsource (lib "*") (part "JM_0"))
    )
    (comp (ref "J2102")
      (value "*")
      (footprint "OPEN")
      (fields (field (name "ALTIUM_UNNAMED_1") "JM"))
      (libsource (lib "*") (part "JM_0"))
    )
    (comp (ref "J2103")
      (value "*")
      (footprint "OPEN")
      (fields (field (name "ALTIUM_UNNAMED_1") "JM"))
      (libsource (lib "*") (part "JM_0"))
    )
    (comp (ref "J2104")
      (value "*")
      (footprint "OPEN")
      (fields (field (name "ALTIUM_UNNAMED_1") "JM"))
      (libsource (lib "*") (part "JM_0"))
    )
    (comp (ref "J2105")
      (value "*")
      (footprint "OPEN")
      (fields (field (name "ALTIUM_UNNAMED_1") "JM"))
      (libsource (lib "*") (part "JM_0"))
    )
    (comp (ref "L2100")
      (value "*")
      (footprint "IND_201610")
      (description "Power Inductor,0.47uH,20%,IND_201610")
      (fields
        (field (name "PCB FOOTPRINT") "IND_201610")
        (field (name "MANUFACTURER") "INPAQ")
        (field (name "TOLERANCE") "0.2")
        (field (name "ALTIUM_UNNAMED_1") "0.47uH")
        (field (name "CREATED BY") "JJJ")
      )
      (libsource (lib "*") (part "INDUCTORS OF FERRITE"))
    )
    (comp (ref "L2101")
      (value "*")
      (footprint "IND_322512")
      (description "Power Inductor,0.22uH,20%,IND_322512")
      (fields
        (field (name "PCB FOOTPRINT") "IND_322512")
        (field (name "TOLERANCE") "0.2")
        (field (name "MANUFACTURER") "TDK")
        (field (name "ALTIUM_UNNAMED_1") "0.22uH")
        (field (name "CREATED BY") "YWQ")
      )
      (libsource (lib "*") (part "INDUCTORS OF FERRITE"))
    )
    (comp (ref "L2102")
      (value "*")
      (footprint "IND_201610")
      (description "Power Inductor,0.47uH,20%,IND_201610")
      (fields
        (field (name "PCB FOOTPRINT") "IND_201610")
        (field (name "MANUFACTURER") "INPAQ")
        (field (name "TOLERANCE") "0.2")
        (field (name "ALTIUM_UNNAMED_1") "0.47uH")
        (field (name "CREATED BY") "JJJ")
      )
      (libsource (lib "*") (part "INDUCTORS OF FERRITE"))
    )
    (comp (ref "L2103")
      (value "*")
      (footprint "IND_322512")
      (description "Power Inductor,0.22uH,20%,IND_322512")
      (fields
        (field (name "PCB FOOTPRINT") "IND_322512")
        (field (name "MANUFACTURER") "TDK")
        (field (name "TOLERANCE") "0.2")
        (field (name "ALTIUM_UNNAMED_1") "0.22uH")
        (field (name "CREATED BY") "YWQ")
      )
      (libsource (lib "*") (part "INDUCTORS OF FERRITE"))
    )
    (comp (ref "L2104")
      (value "*")
      (footprint "IND_201610")
      (description "Power Inductor,0.47uH,20%,IND_201610")
      (fields
        (field (name "PCB FOOTPRINT") "IND_201610")
        (field (name "TOLERANCE") "0.2")
        (field (name "MANUFACTURER") "INPAQ")
        (field (name "ALTIUM_UNNAMED_1") "0.47uH")
        (field (name "CREATED BY") "JJJ")
      )
      (libsource (lib "*") (part "INDUCTORS OF FERRITE"))
    )
    (comp (ref "L2105")
      (value "*")
      (footprint "IND_322512")
      (description "Power Inductor,0.22uH,20%,IND_322512")
      (fields
        (field (name "PCB FOOTPRINT") "IND_322512")
        (field (name "MANUFACTURER") "TDK")
        (field (name "TOLERANCE") "0.2")
        (field (name "ALTIUM_UNNAMED_1") "0.22uH")
        (field (name "CREATED BY") "YWQ")
      )
      (libsource (lib "*") (part "INDUCTORS OF FERRITE"))
    )
    (comp (ref "L2106")
      (value "*")
      (footprint "IND_201610")
      (description "Power Inductor,0.47uH,20%,IND_201610")
      (fields
        (field (name "PCB FOOTPRINT") "IND_201610")
        (field (name "TOLERANCE") "0.2")
        (field (name "MANUFACTURER") "INPAQ")
        (field (name "ALTIUM_UNNAMED_1") "0.47uH")
        (field (name "CREATED BY") "JJJ")
      )
      (libsource (lib "*") (part "INDUCTORS OF FERRITE"))
    )
    (comp (ref "L2107")
      (value "*")
      (footprint "IND_322512")
      (description "Power Inductor,0.22uH,20%,IND_322512")
      (fields
        (field (name "PCB FOOTPRINT") "IND_322512")
        (field (name "TOLERANCE") "0.2")
        (field (name "MANUFACTURER") "TDK")
        (field (name "ALTIUM_UNNAMED_1") "0.22uH")
        (field (name "CREATED BY") "YWQ")
      )
      (libsource (lib "*") (part "INDUCTORS OF FERRITE"))
    )
    (comp (ref "L2108")
      (value "*")
      (footprint "IND_201610")
      (description "Power Inductor,0.47uH,20%,IND_201610")
      (fields
        (field (name "PCB FOOTPRINT") "IND_201610")
        (field (name "MANUFACTURER") "INPAQ")
        (field (name "TOLERANCE") "0.2")
        (field (name "ALTIUM_UNNAMED_1") "0.47uH")
        (field (name "CREATED BY") "JJJ")
      )
      (libsource (lib "*") (part "INDUCTORS OF FERRITE"))
    )
    (comp (ref "L2109")
      (value "*")
      (footprint "IND_201610")
      (description "Power Inductor,0.47uH,20%,IND_201610")
      (fields
        (field (name "PCB FOOTPRINT") "IND_201610")
        (field (name "MANUFACTURER") "INPAQ")
        (field (name "TOLERANCE") "0.2")
        (field (name "ALTIUM_UNNAMED_1") "0.47uH")
        (field (name "CREATED BY") "JJJ")
      )
      (libsource (lib "*") (part "INDUCTORS OF FERRITE"))
    )
    (comp (ref "R2100")
      (value "*")
      (footprint "R0402")
      (description "µзБчјмІвµзЧи,0R01,+/-1%,R1206,1/2W,T.R.C.=ЎА75 ppm/ЎгC")
      (fields
        (field (name "PCB FOOTPRINT") "R1206")
        (field (name "TOLERANCE") "1%")
        (field (name "MANUFACTURER") "YAGEO")
        (field (name "ALTIUM_UNNAMED_1") "0.01R")
        (field (name "CREATED BY") "YTL")
      )
      (libsource (lib "*") (part "RESISTOR_Dup1"))
    )
    (comp (ref "R2101")
      (value "*")
      (footprint "R0402")
      (description "НЁУГєсД¤µзЧи,100K,+/-1%,R0402,1/16W.")
      (fields
        (field (name "PCB FOOTPRINT") "R0402")
        (field (name "TOLERANCE") "1%")
        (field (name "MANUFACTURER") "YAGEO")
        (field (name "ALTIUM_UNNAMED_1") "100K")
        (field (name "CREATED BY") "YTL")
      )
      (libsource (lib "*") (part "RESISTOR"))
    )
    (comp (ref "R2102")
      (value "*")
      (footprint "R0402")
      (description "єсД¤µНЧиЦµµзЧи,0R02,+/-1%,R0805,1/4W.")
      (fields
        (field (name "PCB FOOTPRINT") "R0805")
        (field (name "TOLERANCE") "1%")
        (field (name "MANUFACTURER") "YAGEO")
        (field (name "ALTIUM_UNNAMED_1") "0.02R")
        (field (name "CREATED BY") "YTL")
      )
      (libsource (lib "*") (part "RESISTOR_Dup1"))
    )
    (comp (ref "R2103")
      (value "*")
      (footprint "R0402")
      (description "НЁУГєсД¤µзЧи,120K,+/-1%,R0402,1/16W.")
      (fields
        (field (name "PCB FOOTPRINT") "R0402")
        (field (name "TOLERANCE") "1%")
        (field (name "MANUFACTURER") "YAGEO")
        (field (name "ALTIUM_UNNAMED_1") "120K")
        (field (name "CREATED BY") "YTL")
      )
      (libsource (lib "*") (part "RESISTOR"))
    )
    (comp (ref "R2104")
      (value "*")
      (footprint "R0402")
      (description "НЁУГєсД¤µзЧи,100R,+/-5%,R0402,1/16W.")
      (fields
        (field (name "PCB FOOTPRINT") "R0402")
        (field (name "TOLERANCE") "5%")
        (field (name "MANUFACTURER") "YAGEO")
        (field (name "ALTIUM_UNNAMED_1") "100R")
        (field (name "CREATED BY") "YTL")
      )
      (libsource (lib "*") (part "RESISTOR_Dup1"))
    )
    (comp (ref "R2111")
      (value "*")
      (footprint "R0402")
      (description "єсД¤µНЧиЦµµзЧи,0R01,+/-1%,R0805,1/4W.")
      (fields
        (field (name "PCB FOOTPRINT") "R0805")
        (field (name "TOLERANCE") "1%")
        (field (name "MANUFACTURER") "YAGEO")
        (field (name "ALTIUM_UNNAMED_1") "0.01R")
        (field (name "CREATED BY") "YTL")
      )
      (libsource (lib "*") (part "RESISTOR_Dup1"))
    )
    (comp (ref "R2112")
      (value "*")
      (footprint "R0402")
      (description "µзБчјмІвµзЧи,0R01,+/-1%,R1206,1/2W,T.R.C.=ЎА75 ppm/ЎгC")
      (fields
        (field (name "PCB FOOTPRINT") "R1206")
        (field (name "TOLERANCE") "1%")
        (field (name "MANUFACTURER") "YAGEO")
        (field (name "ALTIUM_UNNAMED_1") "0.01R")
        (field (name "CREATED BY") "YTL")
      )
      (libsource (lib "*") (part "RESISTOR_Dup1"))
    )
    (comp (ref "R2113")
      (value "*")
      (footprint "R0402")
      (description "НЁУГєсД¤µзЧи,100R,+/-5%,R0402,1/16W.")
      (fields
        (field (name "PCB FOOTPRINT") "R0402")
        (field (name "TOLERANCE") "5%")
        (field (name "MANUFACTURER") "YAGEO")
        (field (name "ALTIUM_UNNAMED_1") "100R")
        (field (name "CREATED BY") "YTL")
      )
      (libsource (lib "*") (part "RESISTOR_Dup1"))
    )
    (comp (ref "R2114")
      (value "*")
      (footprint "R0402")
      (description "НЁУГєсД¤µзЧи,100R,+/-5%,R0402,1/16W.")
      (fields
        (field (name "PCB FOOTPRINT") "R0402")
        (field (name "TOLERANCE") "5%")
        (field (name "MANUFACTURER") "YAGEO")
        (field (name "ALTIUM_UNNAMED_1") "100R")
        (field (name "CREATED BY") "YTL")
      )
      (libsource (lib "*") (part "RESISTOR_Dup1"))
    )
    (comp (ref "R2121")
      (value "*")
      (footprint "R0402")
      (description "єсД¤µНЧиЦµµзЧи,0R02,+/-1%,R0805,1/4W.")
      (fields
        (field (name "PCB FOOTPRINT") "R0805")
        (field (name "TOLERANCE") "1%")
        (field (name "MANUFACTURER") "YAGEO")
        (field (name "ALTIUM_UNNAMED_1") "0.02R")
        (field (name "CREATED BY") "YTL")
      )
      (libsource (lib "*") (part "RESISTOR_Dup1"))
    )
    (comp (ref "R2122")
      (value "*")
      (footprint "R0402")
      (description "µзБчјмІвµзЧи,0R01,+/-1%,R1206,1/2W,T.R.C.=ЎА75 ppm/ЎгC")
      (fields
        (field (name "PCB FOOTPRINT") "R1206")
        (field (name "TOLERANCE") "1%")
        (field (name "MANUFACTURER") "YAGEO")
        (field (name "ALTIUM_UNNAMED_1") "0.01R")
        (field (name "CREATED BY") "YTL")
      )
      (libsource (lib "*") (part "RESISTOR_Dup1"))
    )
    (comp (ref "R2123")
      (value "*")
      (footprint "R0402")
      (description "НЁУГєсД¤µзЧи,0R,+/-5%,R0402,1/16W.")
      (fields
        (field (name "PCB FOOTPRINT") "R0402")
        (field (name "TOLERANCE") "5%")
        (field (name "MANUFACTURER") "YAGEO")
        (field (name "ALTIUM_UNNAMED_1") "0R")
        (field (name "CREATED BY") "YTL")
      )
      (libsource (lib "*") (part "RESISTOR_Dup1"))
    )
    (comp (ref "R2124")
      (value "*")
      (footprint "R0402")
      (description "НЁУГєсД¤µзЧи,100R,+/-5%,R0402,1/16W.")
      (fields
        (field (name "PCB FOOTPRINT") "R0402")
        (field (name "TOLERANCE") "5%")
        (field (name "MANUFACTURER") "YAGEO")
        (field (name "ALTIUM_UNNAMED_1") "100R")
        (field (name "CREATED BY") "YTL")
      )
      (libsource (lib "*") (part "RESISTOR_Dup1"))
    )
    (comp (ref "R2125")
      (value "*")
      (footprint "R0402")
      (description "НЁУГєсД¤µзЧи,20K,+/-1%,R0402,1/16W.")
      (fields
        (field (name "PCB FOOTPRINT") "R0402")
        (field (name "TOLERANCE") "1%")
        (field (name "MANUFACTURER") "YAGEO")
        (field (name "ALTIUM_UNNAMED_1") "20K")
        (field (name "CREATED BY") "YTL")
      )
      (libsource (lib "*") (part "RESISTOR"))
    )
    (comp (ref "R2126")
      (value "*")
      (footprint "R0402")
      (description "НЁУГєсД¤µзЧи,100K,+/-1%,R0402,1/16W.")
      (fields
        (field (name "PCB FOOTPRINT") "R0402")
        (field (name "TOLERANCE") "1%")
        (field (name "MANUFACTURER") "YAGEO")
        (field (name "ALTIUM_UNNAMED_1") "100K")
        (field (name "CREATED BY") "YTL")
      )
      (libsource (lib "*") (part "RESISTOR"))
    )
    (comp (ref "R2127")
      (value "*")
      (footprint "R0402")
      (description "єсД¤µНЧиЦµµзЧи,0R02,+/-1%,R0805,1/4W.")
      (fields
        (field (name "PCB FOOTPRINT") "R0805")
        (field (name "TOLERANCE") "1%")
        (field (name "MANUFACTURER") "YAGEO")
        (field (name "ALTIUM_UNNAMED_1") "0.02R")
        (field (name "CREATED BY") "YTL")
      )
      (libsource (lib "*") (part "RESISTOR_Dup1"))
    )
    (comp (ref "R2128")
      (value "*")
      (footprint "R0402")
      (description "µзБчјмІвµзЧи,0R01,+/-1%,R1206,1/2W,T.R.C.=ЎА75 ppm/ЎгC")
      (fields
        (field (name "PCB FOOTPRINT") "R1206")
        (field (name "TOLERANCE") "1%")
        (field (name "MANUFACTURER") "YAGEO")
        (field (name "ALTIUM_UNNAMED_1") "0.01R")
        (field (name "CREATED BY") "YTL")
      )
      (libsource (lib "*") (part "RESISTOR_Dup1"))
    )
    (comp (ref "R2129")
      (value "*")
      (footprint "R0402")
      (description "НЁУГєсД¤µзЧи,100R,+/-5%,R0402,1/16W.")
      (fields
        (field (name "PCB FOOTPRINT") "R0402")
        (field (name "TOLERANCE") "5%")
        (field (name "MANUFACTURER") "YAGEO")
        (field (name "ALTIUM_UNNAMED_1") "100R")
        (field (name "CREATED BY") "YTL")
      )
      (libsource (lib "*") (part "RESISTOR_Dup1"))
    )
    (comp (ref "R2130")
      (value "*")
      (footprint "R0402")
      (description "єсД¤µНЧиЦµµзЧи,0R02,+/-1%,R0805,1/4W.")
      (fields
        (field (name "PCB FOOTPRINT") "R0805")
        (field (name "TOLERANCE") "1%")
        (field (name "MANUFACTURER") "YAGEO")
        (field (name "ALTIUM_UNNAMED_1") "0.02R")
        (field (name "CREATED BY") "YTL")
      )
      (libsource (lib "*") (part "RESISTOR_Dup1"))
    )
    (comp (ref "R2131")
      (value "*")
      (footprint "R0402")
      (description "НЁУГєсД¤µзЧи,0R,+/-5%,R0805,1/8W.")
      (fields
        (field (name "PCB FOOTPRINT") "R0805")
        (field (name "TOLERANCE") "5%")
        (field (name "MANUFACTURER") "YAGEO")
        (field (name "ALTIUM_UNNAMED_1") "0R")
        (field (name "CREATED BY") "YTL")
      )
      (libsource (lib "*") (part "RESISTOR_Dup1"))
    )
    (comp (ref "R2132")
      (value "*")
      (footprint "R0402")
      (description "єсД¤µНЧиЦµµзЧи,0R02,+/-1%,R0603,1/10W.")
      (fields
        (field (name "PCB FOOTPRINT") "R0603")
        (field (name "TOLERANCE") "1%")
        (field (name "MANUFACTURER") "YAGEO")
        (field (name "ALTIUM_UNNAMED_1") "0.02R")
        (field (name "CREATED BY") "YTL")
      )
      (libsource (lib "*") (part "RESISTOR_Dup1"))
    )
    (comp (ref "R2133")
      (value "*")
      (footprint "R0402")
      (description "єсД¤µНЧиЦµµзЧи,0R05,+/-1%,R0603,1/10W.")
      (fields
        (field (name "PCB FOOTPRINT") "R0603")
        (field (name "TOLERANCE") "1%")
        (field (name "MANUFACTURER") "YAGEO")
        (field (name "ALTIUM_UNNAMED_1") "0.05R")
        (field (name "CREATED BY") "YTL")
      )
      (libsource (lib "*") (part "RESISTOR_Dup1"))
    )
    (comp (ref "R2134")
      (value "*")
      (footprint "R0402")
      (description "НЁУГєсД¤µзЧи,100K,+/-5%,R0402,1/16W.")
      (fields
        (field (name "PCB FOOTPRINT") "R0402")
        (field (name "TOLERANCE") "5%")
        (field (name "MANUFACTURER") "YAGEO")
        (field (name "ALTIUM_UNNAMED_1") "100K")
        (field (name "CREATED BY") "YTL")
      )
      (libsource (lib "*") (part "RESISTOR"))
    )
    (comp (ref "R2135")
      (value "*")
      (footprint "R0402")
      (description "єсД¤µНЧиЦµµзЧи,0R02,+/-1%,R0603,1/10W.")
      (fields
        (field (name "PCB FOOTPRINT") "R0603")
        (field (name "TOLERANCE") "1%")
        (field (name "MANUFACTURER") "YAGEO")
        (field (name "ALTIUM_UNNAMED_1") "0.02R")
        (field (name "CREATED BY") "YTL")
      )
      (libsource (lib "*") (part "RESISTOR_Dup1"))
    )
    (comp (ref "R2136")
      (value "*")
      (footprint "R0402")
      (description "НЁУГєсД¤µзЧи,100K,+/-5%,R0402,1/16W.")
      (fields
        (field (name "PCB FOOTPRINT") "R0402")
        (field (name "TOLERANCE") "5%")
        (field (name "MANUFACTURER") "YAGEO")
        (field (name "ALTIUM_UNNAMED_1") "100K")
        (field (name "CREATED BY") "YTL")
      )
      (libsource (lib "*") (part "RESISTOR_Dup1"))
    )
    (comp (ref "R2137")
      (value "*")
      (footprint "R0402")
      (description "НЁУГєсД¤µзЧи,10K,+/-5%,R0402,1/16W.")
      (fields
        (field (name "PCB FOOTPRINT") "R0402")
        (field (name "TOLERANCE") "5%")
        (field (name "MANUFACTURER") "YAGEO")
        (field (name "ALTIUM_UNNAMED_1") "10K")
        (field (name "CREATED BY") "YTL")
      )
      (libsource (lib "*") (part "RESISTOR"))
    )
    (comp (ref "R2138")
      (value "*")
      (footprint "R0402")
      (description "НЁУГєсД¤µзЧи,10K,+/-5%,R0402,1/16W.")
      (fields
        (field (name "PCB FOOTPRINT") "R0402")
        (field (name "TOLERANCE") "5%")
        (field (name "MANUFACTURER") "YAGEO")
        (field (name "ALTIUM_UNNAMED_1") "10K")
        (field (name "CREATED BY") "YTL")
      )
      (libsource (lib "*") (part "RESISTOR"))
    )
    (comp (ref "R2139")
      (value "*")
      (footprint "R0402")
      (description "єсД¤µНЧиЦµµзЧи,0R05,+/-1%,R0603,1/10W.")
      (fields
        (field (name "PCB FOOTPRINT") "R0603")
        (field (name "TOLERANCE") "1%")
        (field (name "MANUFACTURER") "YAGEO")
        (field (name "ALTIUM_UNNAMED_1") "0.05R")
        (field (name "CREATED BY") "YTL")
      )
      (libsource (lib "*") (part "RESISTOR_Dup1"))
    )
    (comp (ref "R2140")
      (value "*")
      (footprint "R0402")
      (description "НЁУГєсД¤µзЧи,100K,+/-5%,R0402,1/16W.")
      (fields
        (field (name "PCB FOOTPRINT") "R0402")
        (field (name "TOLERANCE") "5%")
        (field (name "MANUFACTURER") "YAGEO")
        (field (name "ALTIUM_UNNAMED_1") "100K")
        (field (name "CREATED BY") "YTL")
      )
      (libsource (lib "*") (part "RESISTOR_Dup1"))
    )
    (comp (ref "R2141")
      (value "*")
      (footprint "R0402")
      (description "НЁУГєсД¤µзЧи,0R,+/-5%,R0603,1/10W.")
      (fields
        (field (name "PCB FOOTPRINT") "R0603")
        (field (name "TOLERANCE") "5%")
        (field (name "MANUFACTURER") "YAGEO")
        (field (name "ALTIUM_UNNAMED_1") "0R")
        (field (name "CREATED BY") "YTL")
      )
      (libsource (lib "*") (part "RESISTOR_Dup1"))
    )
    (comp (ref "R2142")
      (value "*")
      (footprint "R0402")
      (description "єсД¤µНЧиЦµµзЧи,0R02,+/-1%,R0603,1/10W.")
      (fields
        (field (name "PCB FOOTPRINT") "R0603")
        (field (name "TOLERANCE") "1%")
        (field (name "MANUFACTURER") "YAGEO")
        (field (name "ALTIUM_UNNAMED_1") "0.02R")
        (field (name "CREATED BY") "YTL")
      )
      (libsource (lib "*") (part "RESISTOR_Dup1"))
    )
    (comp (ref "R2143")
      (value "*")
      (footprint "R0402")
      (description "єсД¤µНЧиЦµµзЧи,0R02,+/-1%,R0603,1/10W.")
      (fields
        (field (name "PCB FOOTPRINT") "R0603")
        (field (name "TOLERANCE") "1%")
        (field (name "MANUFACTURER") "YAGEO")
        (field (name "ALTIUM_UNNAMED_1") "0.02R")
        (field (name "CREATED BY") "YTL")
      )
      (libsource (lib "*") (part "RESISTOR_Dup1"))
    )
    (comp (ref "R2144")
      (value "*")
      (footprint "R0402")
      (description "єсД¤µНЧиЦµµзЧи,0R05,+/-1%,R0603,1/10W.")
      (fields
        (field (name "PCB FOOTPRINT") "R0603")
        (field (name "TOLERANCE") "1%")
        (field (name "MANUFACTURER") "YAGEO")
        (field (name "ALTIUM_UNNAMED_1") "0.05R")
        (field (name "CREATED BY") "YTL")
      )
      (libsource (lib "*") (part "RESISTOR_Dup1"))
    )
    (comp (ref "R2150")
      (value "*")
      (footprint "R0402")
      (description "НЁУГєсД¤µзЧи,100K,+/-5%,R0402,1/16W.")
      (fields
        (field (name "PCB FOOTPRINT") "R0402")
        (field (name "TOLERANCE") "5%")
        (field (name "MANUFACTURER") "YAGEO")
        (field (name "OPTION") "DNP")
        (field (name "ALTIUM_UNNAMED_1") "100K")
        (field (name "CREATED BY") "YTL")
      )
      (libsource (lib "*") (part "RESISTOR"))
    )
    (comp (ref "U2100")
      (value "*")
      (footprint "QFN68_7R00X7R00X0R80_T")
      (description "ROCKCHIP PMIC RK806-1")
      (fields
        (field (name "MANUFACTURER") "Rockchip (ИрРѕОў)")
        (field (name "PCB FOOTPRINT") "QFN68_7R00X7R00X0R80_T")
        (field (name "ALTIUM_UNNAMED_1") "RK806-1")
        (field (name "CREATED BY") "YWQ")
      )
      (libsource (lib "*") (part "PMIC_RK806"))
    )
  )
  (nets
    (net (code "1") (name "/PMIC1_FB6") (class "Default")
      (node (ref "C2101") (pin "2") (pinfunction "2_2") (pintype "passive"))
      (node (ref "R2101") (pin "1") (pinfunction "1_1") (pintype "passive"))
      (node (ref "R2103") (pin "2") (pinfunction "2_2") (pintype "passive"))
      (node (ref "U2100") (pin "31") (pinfunction "FB6_31") (pintype "passive"))
    )
    (net (code "2") (name "/PMIC1_FB9") (class "Default")
      (node (ref "C2137") (pin "2") (pinfunction "2_2") (pintype "passive"))
      (node (ref "R2125") (pin "2") (pinfunction "2_2") (pintype "passive"))
      (node (ref "R2126") (pin "1") (pinfunction "1_1") (pintype "passive"))
      (node (ref "U2100") (pin "66") (pinfunction "FB9_66") (pintype "passive"))
    )
    (net (code "3") (name "/PMIC1_SW1") (class "Default")
      (node (ref "L2101") (pin "1") (pinfunction "1_1") (pintype "passive"))
      (node (ref "U2100") (pin "50") (pinfunction "SW1_1_50") (pintype "passive"))
      (node (ref "U2100") (pin "51") (pinfunction "SW1_2_51") (pintype "passive"))
    )
    (net (code "4") (name "/PMIC1_SW2") (class "Default")
      (node (ref "L2103") (pin "1") (pinfunction "1_1") (pintype "passive"))
      (node (ref "U2100") (pin "35") (pinfunction "SW2_1_35") (pintype "passive"))
      (node (ref "U2100") (pin "36") (pinfunction "SW2_2_36") (pintype "passive"))
    )
    (net (code "5") (name "/PMIC1_SW3") (class "Default")
      (node (ref "L2105") (pin "1") (pinfunction "1_1") (pintype "passive"))
      (node (ref "U2100") (pin "55") (pinfunction "SW3_55") (pintype "passive"))
    )
    (net (code "6") (name "/PMIC1_SW4") (class "Default")
      (node (ref "L2107") (pin "1") (pinfunction "1_1") (pintype "passive"))
      (node (ref "U2100") (pin "23") (pinfunction "SW4_23") (pintype "passive"))
    )
    (net (code "7") (name "/PMIC1_SW5") (class "Default")
      (node (ref "L2102") (pin "2") (pinfunction "2_2") (pintype "passive"))
      (node (ref "U2100") (pin "45") (pinfunction "SW5_45") (pintype "passive"))
    )
    (net (code "8") (name "/PMIC1_SW6") (class "Default")
      (node (ref "L2100") (pin "2") (pinfunction "2_2") (pintype "passive"))
      (node (ref "U2100") (pin "29") (pinfunction "SW6_29") (pintype "passive"))
    )
    (net (code "9") (name "/PMIC1_SW7") (class "Default")
      (node (ref "L2109") (pin "1") (pinfunction "1_1") (pintype "passive"))
      (node (ref "U2100") (pin "42") (pinfunction "SW7_42") (pintype "passive"))
    )
    (net (code "10") (name "/PMIC1_SW8") (class "Default")
      (node (ref "L2106") (pin "2") (pinfunction "2_2") (pintype "passive"))
      (node (ref "U2100") (pin "6") (pinfunction "SW8_6") (pintype "passive"))
    )
    (net (code "11") (name "/PMIC1_SW9") (class "Default")
      (node (ref "L2104") (pin "2") (pinfunction "2_2") (pintype "passive"))
      (node (ref "U2100") (pin "68") (pinfunction "SW9_68") (pintype "passive"))
    )
    (net (code "12") (name "/PMIC1_SW10") (class "Default")
      (node (ref "L2108") (pin "2") (pinfunction "2_2") (pintype "passive"))
      (node (ref "U2100") (pin "26") (pinfunction "SW10_26") (pintype "passive"))
    )
    (net (code "13") (name "/PMIC_VDC") (class "Default")
      (node (ref "C2165") (pin "1") (pinfunction "1_1") (pintype "passive"))
      (node (ref "R2136") (pin "2") (pinfunction "2_2") (pintype "passive"))
      (node (ref "R2140") (pin "1") (pinfunction "1_1") (pintype "passive"))
      (node (ref "U2100") (pin "32") (pinfunction "VDC_32") (pintype "passive"))
    )
    (net (code "14") (name "GND") (class "Default")
      (node (ref "C2100") (pin "2") (pinfunction "2_2") (pintype "passive"))
      (node (ref "C2102") (pin "2") (pinfunction "2_2") (pintype "passive"))
      (node (ref "C2103") (pin "2") (pinfunction "2_2") (pintype "passive"))
      (node (ref "C2104") (pin "2") (pinfunction "2_2") (pintype "passive"))
      (node (ref "C2105") (pin "2") (pinfunction "2_2") (pintype "passive"))
      (node (ref "C2106") (pin "2") (pinfunction "2_2") (pintype "passive"))
      (node (ref "C2107") (pin "2") (pinfunction "2_2") (pintype "passive"))
      (node (ref "C2109") (pin "2") (pinfunction "2_2") (pintype "passive"))
      (node (ref "C2110") (pin "2") (pinfunction "2_2") (pintype "passive"))
      (node (ref "C2111") (pin "2") (pinfunction "2_2") (pintype "passive"))
      (node (ref "C2114") (pin "2") (pinfunction "2_2") (pintype "passive"))
      (node (ref "C2115") (pin "2") (pinfunction "2_2") (pintype "passive"))
      (node (ref "C2116") (pin "2") (pinfunction "2_2") (pintype "passive"))
      (node (ref "C2117") (pin "2") (pinfunction "2_2") (pintype "passive"))
      (node (ref "C2120") (pin "2") (pinfunction "2_2") (pintype "passive"))
      (node (ref "C2121") (pin "2") (pinfunction "2_2") (pintype "passive"))
      (node (ref "C2122") (pin "2") (pinfunction "2_2") (pintype "passive"))
      (node (ref "C2123") (pin "2") (pinfunction "2_2") (pintype "passive"))
      (node (ref "C2126") (pin "2") (pinfunction "2_2") (pintype "passive"))
      (node (ref "C2127") (pin "2") (pinfunction "2_2") (pintype "passive"))
      (node (ref "C2128") (pin "2") (pinfunction "2_2") (pintype "passive"))
      (node (ref "C2129") (pin "2") (pinfunction "2_2") (pintype "passive"))
      (node (ref "C2130") (pin "2") (pinfunction "2_2") (pintype "passive"))
      (node (ref "C2133") (pin "2") (pinfunction "2_2") (pintype "passive"))
      (node (ref "C2134") (pin "2") (pinfunction "2_2") (pintype "passive"))
      (node (ref "C2135") (pin "2") (pinfunction "2_2") (pintype "passive"))
      (node (ref "C2136") (pin "2") (pinfunction "2_2") (pintype "passive"))
      (node (ref "C2138") (pin "2") (pinfunction "2_2") (pintype "passive"))
      (node (ref "C2139") (pin "2") (pinfunction "2_2") (pintype "passive"))
      (node (ref "C2140") (pin "2") (pinfunction "2_2") (pintype "passive"))
      (node (ref "C2141") (pin "2") (pinfunction "2_2") (pintype "passive"))
      (node (ref "C2142") (pin "2") (pinfunction "2_2") (pintype "passive"))
      (node (ref "C2144") (pin "2") (pinfunction "2_2") (pintype "passive"))
      (node (ref "C2145") (pin "2") (pinfunction "2_2") (pintype "passive"))
      (node (ref "C2146") (pin "2") (pinfunction "2_2") (pintype "passive"))
      (node (ref "C2147") (pin "2") (pinfunction "2_2") (pintype "passive"))
      (node (ref "C2148") (pin "2") (pinfunction "2_2") (pintype "passive"))
      (node (ref "C2149") (pin "2") (pinfunction "2_2") (pintype "passive"))
      (node (ref "C2150") (pin "2") (pinfunction "2_2") (pintype "passive"))
      (node (ref "C2151") (pin "2") (pinfunction "2_2") (pintype "passive"))
      (node (ref "C2152") (pin "2") (pinfunction "2_2") (pintype "passive"))
      (node (ref "C2153") (pin "2") (pinfunction "2_2") (pintype "passive"))
      (node (ref "C2154") (pin "2") (pinfunction "2_2") (pintype "passive"))
      (node (ref "C2155") (pin "2") (pinfunction "2_2") (pintype "passive"))
      (node (ref "C2156") (pin "2") (pinfunction "2_2") (pintype "passive"))
      (node (ref "C2157") (pin "2") (pinfunction "2_2") (pintype "passive"))
      (node (ref "C2158") (pin "2") (pinfunction "2_2") (pintype "passive"))
      (node (ref "C2159") (pin "2") (pinfunction "2_2") (pintype "passive"))
      (node (ref "C2160") (pin "2") (pinfunction "2_2") (pintype "passive"))
      (node (ref "C2161") (pin "2") (pinfunction "2_2") (pintype "passive"))
      (node (ref "C2162") (pin "2") (pinfunction "2_2") (pintype "passive"))
      (node (ref "C2163") (pin "2") (pinfunction "2_2") (pintype "passive"))
      (node (ref "C2164") (pin "2") (pinfunction "2_2") (pintype "passive"))
      (node (ref "C2165") (pin "2") (pinfunction "2_2") (pintype "passive"))
      (node (ref "C2166") (pin "2") (pinfunction "2_2") (pintype "passive"))
      (node (ref "C2167") (pin "2") (pinfunction "2_2") (pintype "passive"))
      (node (ref "C2168") (pin "2") (pinfunction "2_2") (pintype "passive"))
      (node (ref "C2169") (pin "2") (pinfunction "2_2") (pintype "passive"))
      (node (ref "C2170") (pin "2") (pinfunction "2_2") (pintype "passive"))
      (node (ref "C2171") (pin "2") (pinfunction "2_2") (pintype "passive"))
      (node (ref "C2172") (pin "2") (pinfunction "2_2") (pintype "passive"))
      (node (ref "C2173") (pin "2") (pinfunction "2_2") (pintype "passive"))
      (node (ref "ED2100") (pin "2") (pinfunction "2_2") (pintype "passive"))
      (node (ref "R2101") (pin "2") (pinfunction "2_2") (pintype "passive"))
      (node (ref "R2126") (pin "2") (pinfunction "2_2") (pintype "passive"))
      (node (ref "R2134") (pin "2") (pinfunction "2_2") (pintype "passive"))
      (node (ref "R2140") (pin "2") (pinfunction "2_2") (pintype "passive"))
      (node (ref "R2150") (pin "2") (pinfunction "2_2") (pintype "passive"))
      (node (ref "U2100") (pin "69") (pinfunction "ePAD_69") (pintype "passive"))
    )
    (net (code "15") (name "PMIC_EXT_EN_OUT") (class "Default")
      (node (ref "U2100") (pin "39") (pinfunction "(~{M}/S)EXT_EN_39") (pintype "passive"))
    )
    (net (code "16") (name "PMIC_INT_L") (class "Default")
      (node (ref "R2137") (pin "2") (pinfunction "2_2") (pintype "passive"))
      (node (ref "U2100") (pin "19") (pinfunction "INT_19") (pintype "passive"))
    )
    (net (code "17") (name "PMIC_PWR_CTRL1") (class "Default")
      (node (ref "U2100") (pin "62") (pinfunction "PWRCTRL1_62") (pintype "passive"))
    )
    (net (code "18") (name "PMIC_PWR_CTRL2") (class "Default")
      (node (ref "U2100") (pin "61") (pinfunction "PWRCTRL2_61") (pintype "passive"))
    )
    (net (code "19") (name "PMIC_PWR_CTRL3") (class "Default")
      (node (ref "U2100") (pin "16") (pinfunction "(PWRCTRL3)SO_16") (pintype "passive"))
    )
    (net (code "20") (name "PMIC_SPI_CLK") (class "Default")
      (node (ref "U2100") (pin "17") (pinfunction "(SCL)CLK_17") (pintype "passive"))
    )
    (net (code "21") (name "PMIC_SPI_CS") (class "Default")
      (node (ref "R2134") (pin "1") (pinfunction "1_1") (pintype "passive"))
      (node (ref "U2100") (pin "18") (pinfunction "(IIC/~{SPI})CS_18") (pintype "passive"))
    )
    (net (code "22") (name "PMIC_SPI_MOSI") (class "Default")
      (node (ref "R2150") (pin "1") (pinfunction "1_1") (pintype "passive"))
      (node (ref "U2100") (pin "15") (pinfunction "(SDA)MOSI_15") (pintype "passive"))
    )
    (net (code "23") (name "RESET_L") (class "Default")
      (node (ref "C2166") (pin "1") (pinfunction "1_1") (pintype "passive"))
      (node (ref "R2138") (pin "2") (pinfunction "2_2") (pintype "passive"))
      (node (ref "U2100") (pin "40") (pinfunction "RESETB_40") (pintype "passive"))
    )
    (net (code "24") (name "VCC4V0_SYS") (class "Default")
      (node (ref "C2103") (pin "1") (pinfunction "1_1") (pintype "passive"))
      (node (ref "C2104") (pin "1") (pinfunction "1_1") (pintype "passive"))
      (node (ref "C2105") (pin "1") (pinfunction "1_1") (pintype "passive"))
      (node (ref "C2114") (pin "1") (pinfunction "1_1") (pintype "passive"))
      (node (ref "C2126") (pin "1") (pinfunction "1_1") (pintype "passive"))
      (node (ref "C2127") (pin "1") (pinfunction "1_1") (pintype "passive"))
      (node (ref "C2138") (pin "1") (pinfunction "1_1") (pintype "passive"))
      (node (ref "C2139") (pin "1") (pinfunction "1_1") (pintype "passive"))
      (node (ref "C2147") (pin "1") (pinfunction "1_1") (pintype "passive"))
      (node (ref "C2148") (pin "1") (pinfunction "1_1") (pintype "passive"))
      (node (ref "C2161") (pin "1") (pinfunction "1_1") (pintype "passive"))
      (node (ref "C2162") (pin "1") (pinfunction "1_1") (pintype "passive"))
      (node (ref "ED2100") (pin "1") (pinfunction "1_1") (pintype "passive"))
      (node (ref "R2136") (pin "1") (pinfunction "1_1") (pintype "passive"))
      (node (ref "U2100") (pin "1") (pinfunction "VCC9_1") (pintype "passive"))
      (node (ref "U2100") (pin "21") (pinfunction "VCCA_21") (pintype "passive"))
      (node (ref "U2100") (pin "22") (pinfunction "VCC4_22") (pintype "passive"))
      (node (ref "U2100") (pin "27") (pinfunction "VCC10_27") (pintype "passive"))
      (node (ref "U2100") (pin "28") (pinfunction "VCC6_28") (pintype "passive"))
      (node (ref "U2100") (pin "33") (pinfunction "VCC2_1_33") (pintype "passive"))
      (node (ref "U2100") (pin "34") (pinfunction "VCC2_2_34") (pintype "passive"))
      (node (ref "U2100") (pin "43") (pinfunction "VCC7_43") (pintype "passive"))
      (node (ref "U2100") (pin "44") (pinfunction "VCC5_44") (pintype "passive"))
      (node (ref "U2100") (pin "52") (pinfunction "VCC1_1_52") (pintype "passive"))
      (node (ref "U2100") (pin "53") (pinfunction "VCC1_2_53") (pintype "passive"))
      (node (ref "U2100") (pin "54") (pinfunction "VCC3_54") (pintype "passive"))
      (node (ref "U2100") (pin "64") (pinfunction "VCC12_64") (pintype "passive"))
      (node (ref "U2100") (pin "7") (pinfunction "VCC8_7") (pintype "passive"))
    )
    (net (code "25") (name "VCCA1V2_IMAGE") (class "Default")
      (node (ref "C2159") (pin "1") (pinfunction "1_1") (pintype "passive"))
      (node (ref "U2100") (pin "57") (pinfunction "PLDO3_57") (pintype "passive"))
    )
    (net (code "26") (name "VCCA1V8_IMAGE") (class "Default")
      (node (ref "R2133") (pin "2") (pinfunction "2_2") (pintype "passive"))
    )
    (net (code "27") (name "VCCA1V8_IMAGE_P") (class "Default")
      (node (ref "C2157") (pin "1") (pinfunction "1_1") (pintype "passive"))
      (node (ref "R2133") (pin "1") (pinfunction "1_1") (pintype "passive"))
      (node (ref "U2100") (pin "58") (pinfunction "PLDO2_58") (pintype "passive"))
    )
    (net (code "28") (name "VCCA1V8_PLDO6") (class "Default")
      (node (ref "C2158") (pin "1") (pinfunction "1_1") (pintype "passive"))
      (node (ref "U2100") (pin "20") (pinfunction "VCCIO_20") (pintype "passive"))
    )
    (net (code "29") (name "VCCA_1V8") (class "Default")
      (node (ref "R2132") (pin "2") (pinfunction "2_2") (pintype "passive"))
    )
    (net (code "30") (name "VCCA_1V8_P") (class "Default")
      (node (ref "C2155") (pin "1") (pinfunction "1_1") (pintype "passive"))
      (node (ref "R2132") (pin "1") (pinfunction "1_1") (pintype "passive"))
      (node (ref "U2100") (pin "60") (pinfunction "PLDO1_60") (pintype "passive"))
    )
    (net (code "31") (name "VCCA_3V3") (class "Default")
      (node (ref "R2135") (pin "2") (pinfunction "2_2") (pintype "passive"))
    )
    (net (code "32") (name "VCCA_3V3_P") (class "Default")
      (node (ref "C2160") (pin "1") (pinfunction "1_1") (pintype "passive"))
      (node (ref "R2135") (pin "1") (pinfunction "1_1") (pintype "passive"))
      (node (ref "U2100") (pin "63") (pinfunction "PLDO4_63") (pintype "passive"))
    )
    (net (code "33") (name "VCCIO_SD_P") (class "Default")
      (node (ref "C2163") (pin "1") (pinfunction "1_1") (pintype "passive"))
      (node (ref "U2100") (pin "65") (pinfunction "PLDO5_65") (pintype "passive"))
    )
    (net (code "34") (name "VCC_1V1_NLDO") (class "Default")
      (node (ref "C2167") (pin "1") (pinfunction "1_1") (pintype "passive"))
      (node (ref "C2171") (pin "1") (pinfunction "1_1") (pintype "passive"))
      (node (ref "U2100") (pin "13") (pinfunction "VCC13_13") (pintype "passive"))
      (node (ref "U2100") (pin "9") (pinfunction "VCC14_9") (pintype "passive"))
    )
    (net (code "35") (name "VCC_1V8") (class "Default")
      (node (ref "C2149") (pin "1") (pinfunction "1_1") (pintype "passive"))
      (node (ref "R2130") (pin "1") (pinfunction "1_1") (pintype "passive"))
      (node (ref "R2137") (pin "1") (pinfunction "1_1") (pintype "passive"))
      (node (ref "R2138") (pin "1") (pinfunction "1_1") (pintype "passive"))
    )
    (net (code "36") (name "VCC_1V8_P") (class "Default")
      (node (ref "C2150") (pin "1") (pinfunction "1_1") (pintype "passive"))
      (node (ref "C2151") (pin "1") (pinfunction "1_1") (pintype "passive"))
      (node (ref "L2108") (pin "1") (pinfunction "1_1") (pintype "passive"))
      (node (ref "R2130") (pin "2") (pinfunction "2_2") (pintype "passive"))
      (node (ref "U2100") (pin "25") (pinfunction "VOUT10_25") (pintype "passive"))
    )
    (net (code "37") (name "VCC_2V0_PLDO") (class "Default")
      (node (ref "C2154") (pin "1") (pinfunction "1_1") (pintype "passive"))
      (node (ref "C2156") (pin "1") (pinfunction "1_1") (pintype "passive"))
      (node (ref "R2131") (pin "2") (pinfunction "2_2") (pintype "passive"))
      (node (ref "U2100") (pin "59") (pinfunction "VCC11_59") (pintype "passive"))
    )
    (net (code "38") (name "VCC_2V0_PLDO_P") (class "Default")
      (node (ref "C2152") (pin "1") (pinfunction "1_1") (pintype "passive"))
      (node (ref "C2153") (pin "1") (pinfunction "1_1") (pintype "passive"))
      (node (ref "L2109") (pin "2") (pinfunction "2_2") (pintype "passive"))
      (node (ref "R2131") (pin "1") (pinfunction "1_1") (pintype "passive"))
      (node (ref "U2100") (pin "41") (pinfunction "VOUT7_41") (pintype "passive"))
    )
    (net (code "39") (name "VCC_3V3") (class "Default")
      (node (ref "C2140") (pin "1") (pinfunction "1_1") (pintype "passive"))
      (node (ref "R2127") (pin "1") (pinfunction "1_1") (pintype "passive"))
    )
    (net (code "40") (name "VCC_3V3_P") (class "Default")
      (node (ref "C2141") (pin "1") (pinfunction "1_1") (pintype "passive"))
      (node (ref "C2142") (pin "1") (pinfunction "1_1") (pintype "passive"))
      (node (ref "L2106") (pin "1") (pinfunction "1_1") (pintype "passive"))
      (node (ref "R2127") (pin "2") (pinfunction "2_2") (pintype "passive"))
      (node (ref "U2100") (pin "5") (pinfunction "VOUT8_5") (pintype "passive"))
    )
    (net (code "41") (name "VDD2_DDR") (class "Default")
      (node (ref "C2100") (pin "1") (pinfunction "1_1") (pintype "passive"))
      (node (ref "R2102") (pin "1") (pinfunction "1_1") (pintype "passive"))
    )
    (net (code "42") (name "VDD2_DDR_P") (class "Default")
      (node (ref "C2101") (pin "1") (pinfunction "1_1") (pintype "passive"))
      (node (ref "C2106") (pin "1") (pinfunction "1_1") (pintype "passive"))
      (node (ref "C2107") (pin "1") (pinfunction "1_1") (pintype "passive"))
      (node (ref "L2100") (pin "1") (pinfunction "1_1") (pintype "passive"))
      (node (ref "R2102") (pin "2") (pinfunction "2_2") (pintype "passive"))
      (node (ref "R2103") (pin "1") (pinfunction "1_1") (pintype "passive"))
      (node (ref "U2100") (pin "30") (pinfunction "VOUT6_30") (pintype "passive"))
    )
    (net (code "43") (name "VDDA0V75_IMAGE") (class "Default")
      (node (ref "R2142") (pin "2") (pinfunction "2_2") (pintype "passive"))
    )
    (net (code "44") (name "VDDA0V75_IMAGE_P") (class "Default")
      (node (ref "C2169") (pin "1") (pinfunction "1_1") (pintype "passive"))
      (node (ref "R2142") (pin "1") (pinfunction "1_1") (pintype "passive"))
      (node (ref "U2100") (pin "11") (pinfunction "NLDO3_11") (pintype "passive"))
    )
    (net (code "45") (name "VDDA_0V75") (class "Default")
      (node (ref "R2144") (pin "2") (pinfunction "2_2") (pintype "passive"))
    )
    (net (code "46") (name "VDDA_0V75_P") (class "Default")
      (node (ref "C2172") (pin "1") (pinfunction "1_1") (pintype "passive"))
      (node (ref "R2144") (pin "1") (pinfunction "1_1") (pintype "passive"))
      (node (ref "U2100") (pin "8") (pinfunction "NLDO5_8") (pintype "passive"))
    )
    (net (code "47") (name "VDDA_0V75_PMU") (class "Default")
      (node (ref "R2139") (pin "2") (pinfunction "2_2") (pintype "passive"))
    )
    (net (code "48") (name "VDDA_0V75_PMU_P") (class "Default")
      (node (ref "C2164") (pin "1") (pinfunction "1_1") (pintype "passive"))
      (node (ref "R2139") (pin "1") (pinfunction "1_1") (pintype "passive"))
      (node (ref "U2100") (pin "14") (pinfunction "NLDO1_14") (pintype "passive"))
    )
    (net (code "49") (name "VDDA_0V85") (class "Default")
      (node (ref "R2143") (pin "2") (pinfunction "2_2") (pintype "passive"))
    )
    (net (code "50") (name "VDDA_0V85_P") (class "Default")
      (node (ref "C2170") (pin "1") (pinfunction "1_1") (pintype "passive"))
      (node (ref "R2143") (pin "1") (pinfunction "1_1") (pintype "passive"))
      (node (ref "U2100") (pin "10") (pinfunction "NLDO4_10") (pintype "passive"))
    )
    (net (code "51") (name "VDDA_DDR_PLL") (class "Default")
      (node (ref "R2141") (pin "2") (pinfunction "2_2") (pintype "passive"))
    )
    (net (code "52") (name "VDDA_DDR_PLL_P") (class "Default")
      (node (ref "C2168") (pin "1") (pinfunction "1_1") (pintype "passive"))
      (node (ref "R2141") (pin "1") (pinfunction "1_1") (pintype "passive"))
      (node (ref "U2100") (pin "12") (pinfunction "NLDO2_12") (pintype "passive"))
    )
    (net (code "53") (name "VDDQ_DDR") (class "Default")
      (node (ref "C2128") (pin "1") (pinfunction "1_1") (pintype "passive"))
      (node (ref "C2131") (pin "2") (pinfunction "2_2") (pintype "passive"))
      (node (ref "C2137") (pin "1") (pinfunction "1_1") (pintype "passive"))
      (node (ref "J2101") (pin "1") (pinfunction "1_1") (pintype "passive"))
      (node (ref "R2121") (pin "1") (pinfunction "1_1") (pintype "passive"))
      (node (ref "R2123") (pin "2") (pinfunction "2_2") (pintype "passive"))
      (node (ref "R2125") (pin "1") (pinfunction "1_1") (pintype "passive"))
      (node (ref "U2100") (pin "67") (pinfunction "VOUT9_67") (pintype "passive"))
    )
    (net (code "54") (name "VDDQ_DDR_P") (class "Default")
      (node (ref "C2129") (pin "1") (pinfunction "1_1") (pintype "passive"))
      (node (ref "C2130") (pin "1") (pinfunction "1_1") (pintype "passive"))
      (node (ref "C2131") (pin "1") (pinfunction "1_1") (pintype "passive"))
      (node (ref "J2101") (pin "2") (pinfunction "2_2") (pintype "passive"))
      (node (ref "L2104") (pin "1") (pinfunction "1_1") (pintype "passive"))
      (node (ref "R2121") (pin "2") (pinfunction "2_2") (pintype "passive"))
      (node (ref "R2123") (pin "1") (pinfunction "1_1") (pintype "passive"))
    )
    (net (code "55") (name "VDD_CPU_LIT") (class "Default")
      (node (ref "C2119") (pin "2") (pinfunction "2_2") (pintype "passive"))
      (node (ref "C2122") (pin "1") (pinfunction "1_1") (pintype "passive"))
      (node (ref "C2123") (pin "1") (pinfunction "1_1") (pintype "passive"))
      (node (ref "J2103") (pin "2") (pinfunction "2_2") (pintype "passive"))
      (node (ref "R2112") (pin "2") (pinfunction "2_2") (pintype "passive"))
      (node (ref "R2114") (pin "2") (pinfunction "2_2") (pintype "passive"))
      (node (ref "U2100") (pin "37") (pinfunction "VOUT2_37") (pintype "passive"))
    )
    (net (code "56") (name "VDD_CPU_LIT_P") (class "Default")
      (node (ref "C2119") (pin "1") (pinfunction "1_1") (pintype "passive"))
      (node (ref "C2120") (pin "1") (pinfunction "1_1") (pintype "passive"))
      (node (ref "C2121") (pin "1") (pinfunction "1_1") (pintype "passive"))
      (node (ref "J2103") (pin "1") (pinfunction "1_1") (pintype "passive"))
      (node (ref "L2103") (pin "2") (pinfunction "2_2") (pintype "passive"))
      (node (ref "R2112") (pin "1") (pinfunction "1_1") (pintype "passive"))
      (node (ref "R2114") (pin "1") (pinfunction "1_1") (pintype "passive"))
    )
    (net (code "57") (name "VDD_DDR") (class "Default")
      (node (ref "C2115") (pin "1") (pinfunction "1_1") (pintype "passive"))
      (node (ref "C2118") (pin "2") (pinfunction "2_2") (pintype "passive"))
      (node (ref "J2100") (pin "1") (pinfunction "1_1") (pintype "passive"))
      (node (ref "R2111") (pin "1") (pinfunction "1_1") (pintype "passive"))
      (node (ref "R2113") (pin "2") (pinfunction "2_2") (pintype "passive"))
      (node (ref "U2100") (pin "46") (pinfunction "VOUT5_46") (pintype "passive"))
    )
    (net (code "58") (name "VDD_DDR_P") (class "Default")
      (node (ref "C2116") (pin "1") (pinfunction "1_1") (pintype "passive"))
      (node (ref "C2117") (pin "1") (pinfunction "1_1") (pintype "passive"))
      (node (ref "C2118") (pin "1") (pinfunction "1_1") (pintype "passive"))
      (node (ref "J2100") (pin "2") (pinfunction "2_2") (pintype "passive"))
      (node (ref "L2102") (pin "1") (pinfunction "1_1") (pintype "passive"))
      (node (ref "R2111") (pin "2") (pinfunction "2_2") (pintype "passive"))
      (node (ref "R2113") (pin "1") (pinfunction "1_1") (pintype "passive"))
    )
    (net (code "59") (name "VDD_GPU") (class "Default")
      (node (ref "C2102") (pin "1") (pinfunction "1_1") (pintype "passive"))
      (node (ref "C2108") (pin "2") (pinfunction "2_2") (pintype "passive"))
      (node (ref "C2111") (pin "1") (pinfunction "1_1") (pintype "passive"))
      (node (ref "J2102") (pin "2") (pinfunction "2_2") (pintype "passive"))
      (node (ref "R2100") (pin "2") (pinfunction "2_2") (pintype "passive"))
      (node (ref "R2104") (pin "2") (pinfunction "2_2") (pintype "passive"))
      (node (ref "U2100") (pin "49") (pinfunction "VOUT1_49") (pintype "passive"))
    )
    (net (code "60") (name "VDD_GPU_P") (class "Default")
      (node (ref "C2108") (pin "1") (pinfunction "1_1") (pintype "passive"))
      (node (ref "C2109") (pin "1") (pinfunction "1_1") (pintype "passive"))
      (node (ref "C2110") (pin "1") (pinfunction "1_1") (pintype "passive"))
      (node (ref "J2102") (pin "1") (pinfunction "1_1") (pintype "passive"))
      (node (ref "L2101") (pin "2") (pinfunction "2_2") (pintype "passive"))
      (node (ref "R2100") (pin "1") (pinfunction "1_1") (pintype "passive"))
      (node (ref "R2104") (pin "1") (pinfunction "1_1") (pintype "passive"))
    )
    (net (code "61") (name "VDD_LOGIC") (class "Default")
      (node (ref "C2132") (pin "2") (pinfunction "2_2") (pintype "passive"))
      (node (ref "C2135") (pin "1") (pinfunction "1_1") (pintype "passive"))
      (node (ref "C2136") (pin "1") (pinfunction "1_1") (pintype "passive"))
      (node (ref "J2104") (pin "2") (pinfunction "2_2") (pintype "passive"))
      (node (ref "R2122") (pin "2") (pinfunction "2_2") (pintype "passive"))
      (node (ref "R2124") (pin "2") (pinfunction "2_2") (pintype "passive"))
      (node (ref "U2100") (pin "56") (pinfunction "VOUT3_56") (pintype "passive"))
    )
    (net (code "62") (name "VDD_LOGIC_P") (class "Default")
      (node (ref "C2132") (pin "1") (pinfunction "1_1") (pintype "passive"))
      (node (ref "C2133") (pin "1") (pinfunction "1_1") (pintype "passive"))
      (node (ref "C2134") (pin "1") (pinfunction "1_1") (pintype "passive"))
      (node (ref "J2104") (pin "1") (pinfunction "1_1") (pintype "passive"))
      (node (ref "L2105") (pin "2") (pinfunction "2_2") (pintype "passive"))
      (node (ref "R2122") (pin "1") (pinfunction "1_1") (pintype "passive"))
      (node (ref "R2124") (pin "1") (pinfunction "1_1") (pintype "passive"))
    )
    (net (code "63") (name "VDD_VDENC") (class "Default")
      (node (ref "C2143") (pin "2") (pinfunction "2_2") (pintype "passive"))
      (node (ref "C2146") (pin "1") (pinfunction "1_1") (pintype "passive"))
      (node (ref "C2173") (pin "1") (pinfunction "1_1") (pintype "passive"))
      (node (ref "J2105") (pin "2") (pinfunction "2_2") (pintype "passive"))
      (node (ref "R2128") (pin "2") (pinfunction "2_2") (pintype "passive"))
      (node (ref "R2129") (pin "2") (pinfunction "2_2") (pintype "passive"))
      (node (ref "U2100") (pin "24") (pinfunction "VOUT4_24") (pintype "passive"))
    )
    (net (code "64") (name "VDD_VDENC_P") (class "Default")
      (node (ref "C2143") (pin "1") (pinfunction "1_1") (pintype "passive"))
      (node (ref "C2144") (pin "1") (pinfunction "1_1") (pintype "passive"))
      (node (ref "C2145") (pin "1") (pinfunction "1_1") (pintype "passive"))
      (node (ref "J2105") (pin "1") (pinfunction "1_1") (pintype "passive"))
      (node (ref "L2107") (pin "2") (pinfunction "2_2") (pintype "passive"))
      (node (ref "R2128") (pin "1") (pinfunction "1_1") (pintype "passive"))
      (node (ref "R2129") (pin "1") (pinfunction "1_1") (pintype "passive"))
    )
    (net (code "65") (name "unconnected-(U2100A-FB1-Pad48)") (class "Default")
      (node (ref "U2100") (pin "48") (pinfunction "FB1_48") (pintype "passive+no_connect"))
    )
    (net (code "66") (name "unconnected-(U2100A-FB2-Pad38)") (class "Default")
      (node (ref "U2100") (pin "38") (pinfunction "FB2_38") (pintype "passive+no_connect"))
    )
    (net (code "67") (name "unconnected-(U2100A-FB5-Pad47)") (class "Default")
      (node (ref "U2100") (pin "47") (pinfunction "FB5_47") (pintype "passive+no_connect"))
    )
    (net (code "68") (name "unconnected-(U2100C-PWRON-Pad4)") (class "Default")
      (node (ref "U2100") (pin "4") (pinfunction "PWRON_4") (pintype "passive+no_connect"))
    )
    (net (code "69") (name "unconnected-(U2100C-SYNC-Pad2)") (class "Default")
      (node (ref "U2100") (pin "2") (pinfunction "SYNC_2") (pintype "passive+no_connect"))
    )
    (net (code "70") (name "unconnected-(U2100C-SYNC_CLK-Pad3)") (class "Default")
      (node (ref "U2100") (pin "3") (pinfunction "SYNC_CLK_3") (pintype "passive+no_connect"))
    )
  )
)
